# Inverter_540VDC_V2_1.net
KiCad netlist of a schematic drawn in Altium Designer
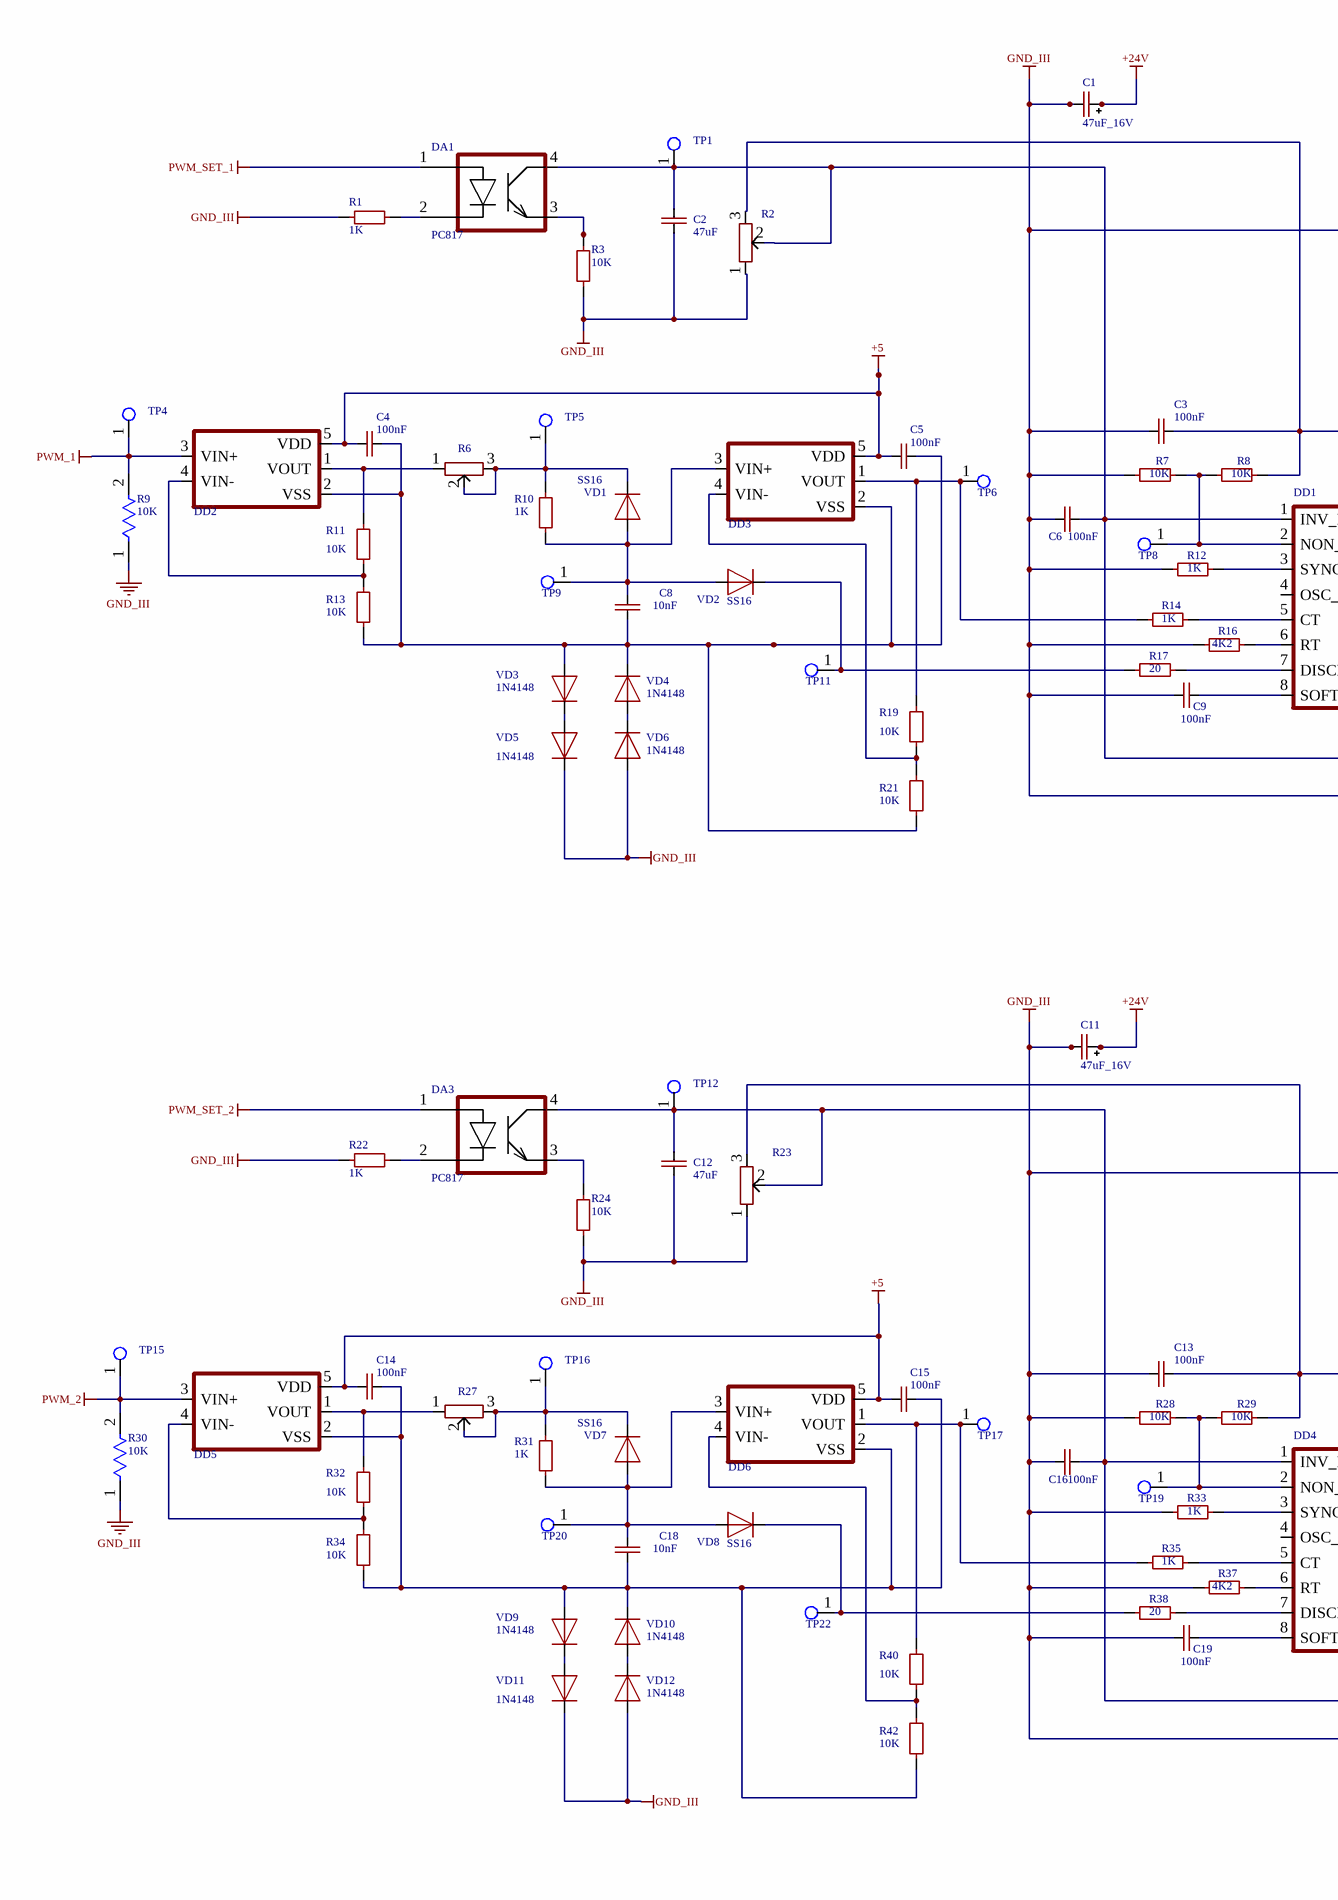
[diagram p0: Inverter_540VDC_V2.1.SchDoc, top left]
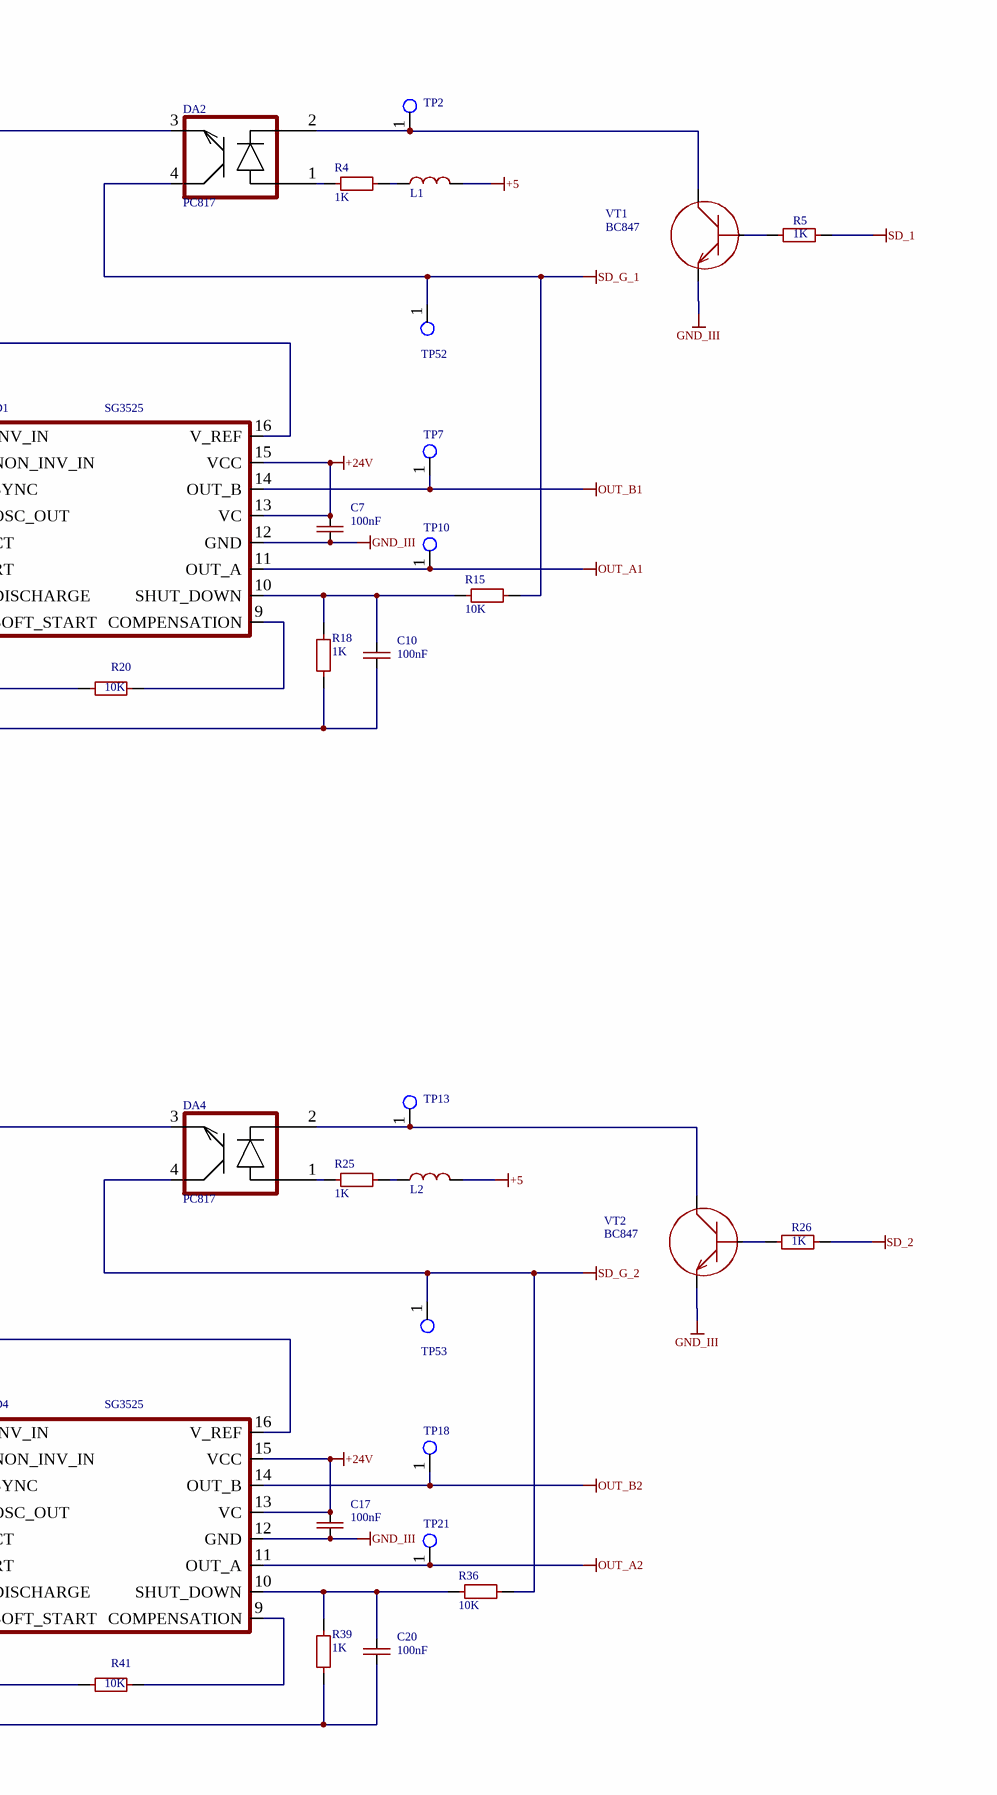
[diagram p1: Inverter_540VDC_V2.1.SchDoc, top right]
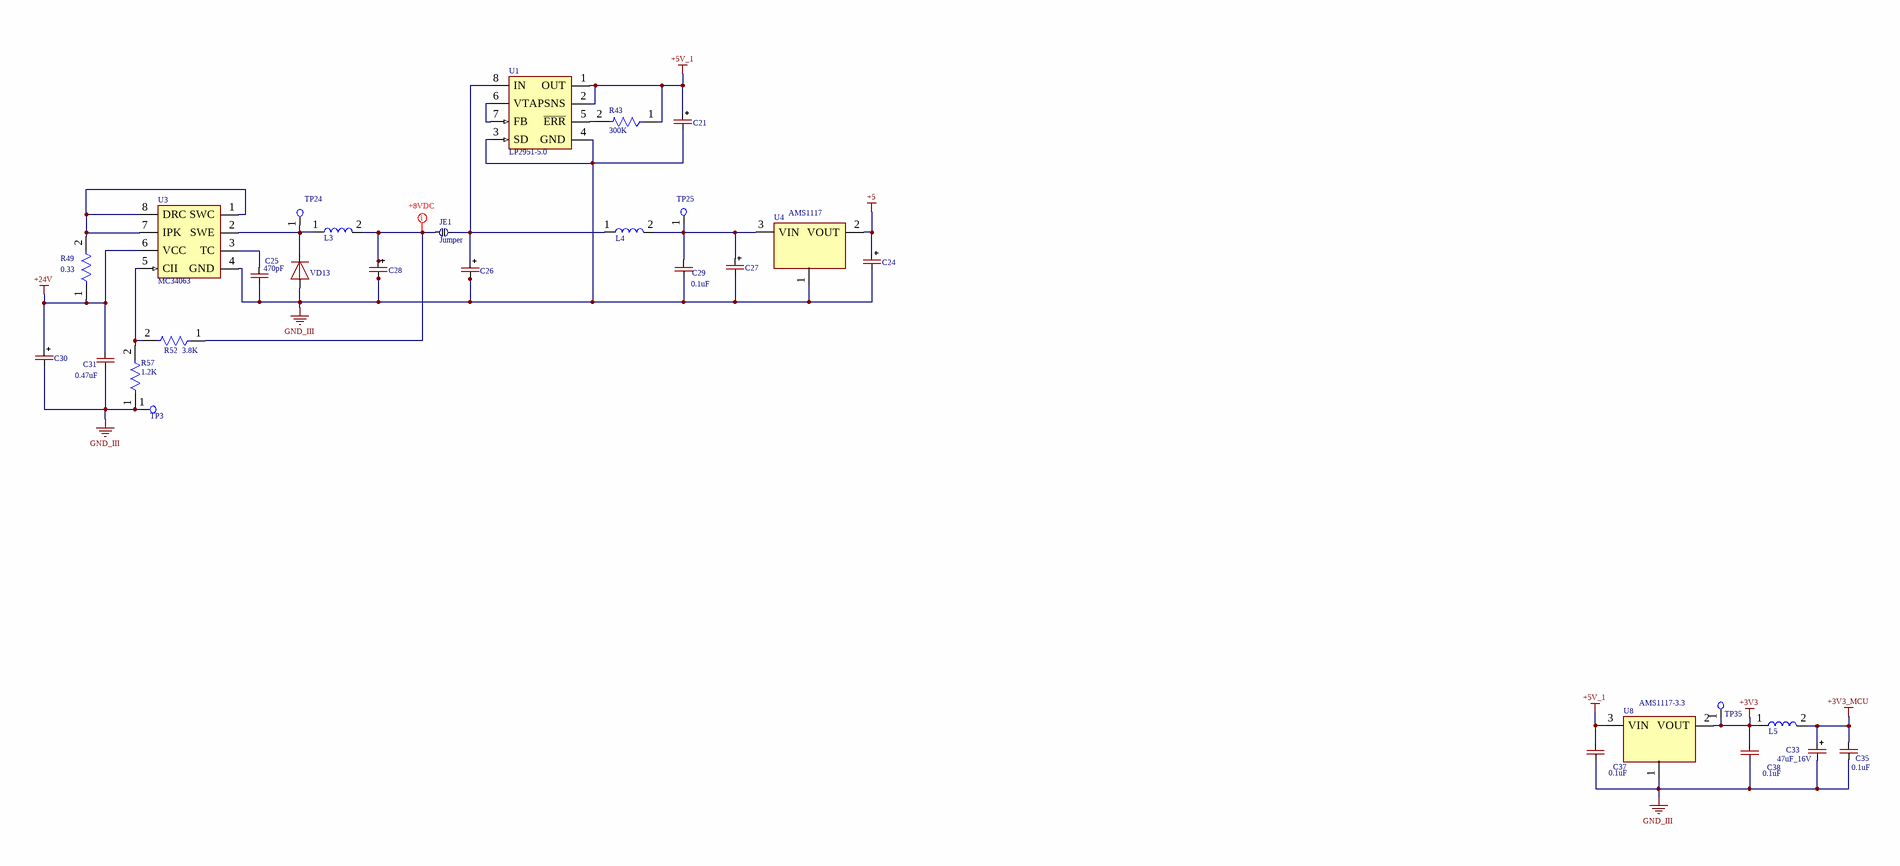
[diagram p2: Inverter_540VDC_V2.1.SchDoc, bottom left]
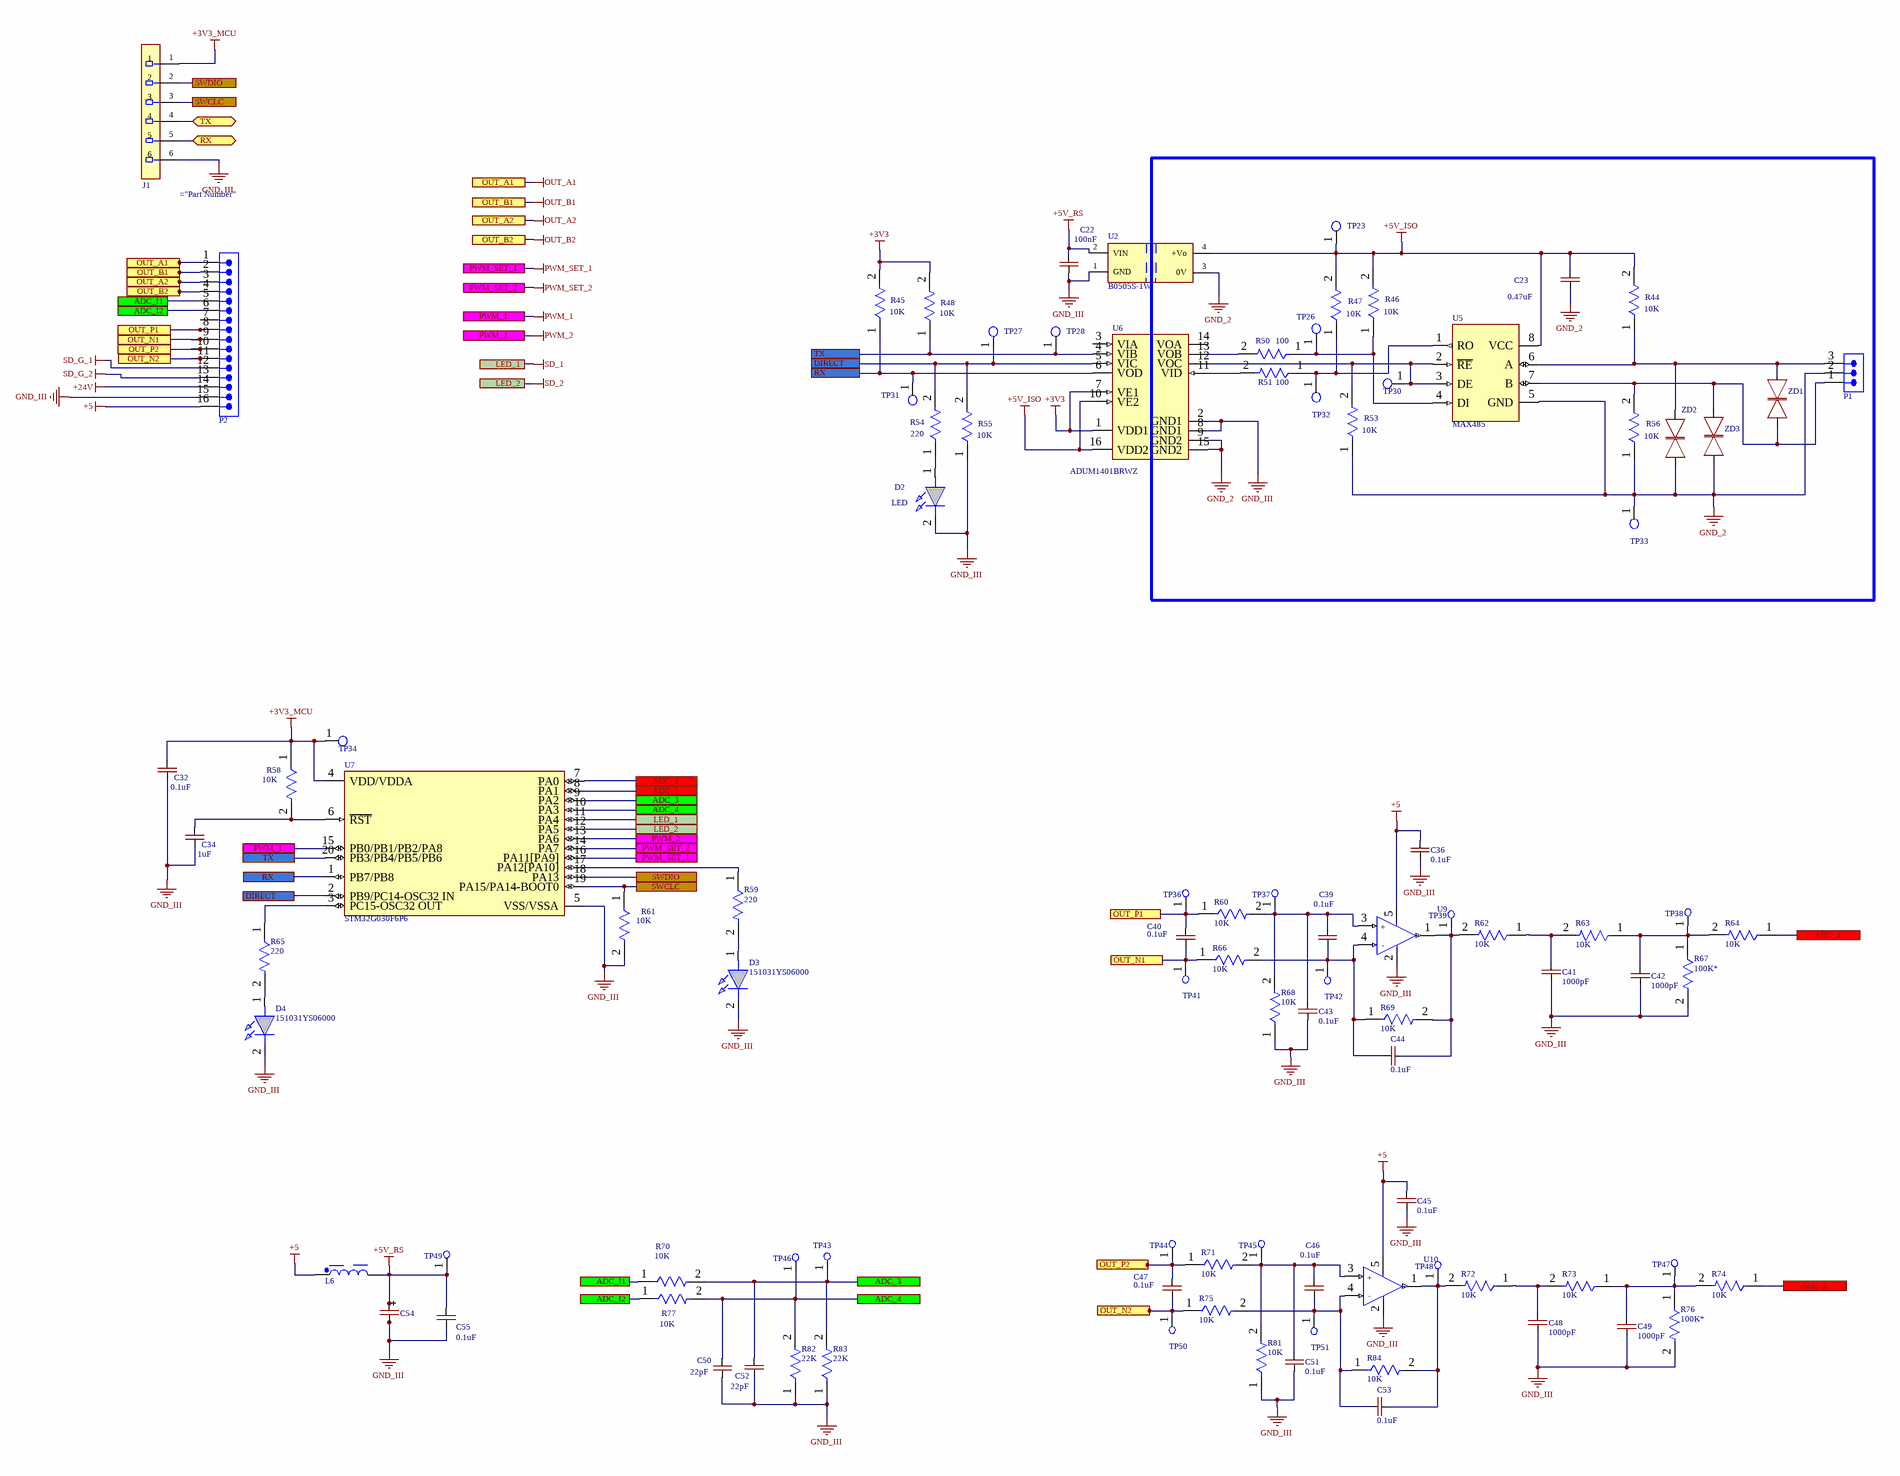
[diagram p3: Inverter_540VDC_V2.1.SchDoc, bottom right]

(export (version "E")
  (design (tool "Eeschema 10.0.6"))
  (components
    (comp (ref "C1")
      (value "47uF_16V")
      (footprint "CAP-TAN-D")
      (libsource (lib "PASSIVE_COMPONENTS") (part "CAP-POLAR"))
    )
    (comp (ref "C2")
      (value "47uF")
      (footprint "CAP-0805")
      (libsource (lib "PAS_COMPONENTS") (part "CAP-NON-POLAR"))
    )
    (comp (ref "C3")
      (value "100nF")
      (footprint "CAP-0805")
      (libsource (lib "PAS_COMPONENTS") (part "CAP-NON-POLAR"))
    )
    (comp (ref "C4")
      (value "100nF")
      (footprint "CAP-0805")
      (libsource (lib "PAS_COMPONENTS") (part "CAP-NON-POLAR"))
    )
    (comp (ref "C5")
      (value "100nF")
      (footprint "CAP-0805")
      (libsource (lib "PAS_COMPONENTS") (part "CAP-NON-POLAR"))
    )
    (comp (ref "C6")
      (value "100nF")
      (footprint "CAP-0805")
      (libsource (lib "PAS_COMPONENTS") (part "CAP-NON-POLAR"))
    )
    (comp (ref "C7")
      (value "100nF")
      (footprint "CAP-0805")
      (libsource (lib "PAS_COMPONENTS") (part "CAP-NON-POLAR"))
    )
    (comp (ref "C8")
      (value "10nF")
      (footprint "CAP-0805")
      (libsource (lib "PAS_COMPONENTS") (part "CAP-NON-POLAR"))
    )
    (comp (ref "C9")
      (value "100nF")
      (footprint "CAP-0805")
      (libsource (lib "PAS_COMPONENTS") (part "CAP-NON-POLAR"))
    )
    (comp (ref "C10")
      (value "100nF")
      (footprint "CAP-0805")
      (libsource (lib "PAS_COMPONENTS") (part "CAP-NON-POLAR"))
    )
    (comp (ref "C11")
      (value "47uF_16V")
      (footprint "CAP-TAN-D")
      (libsource (lib "PASSIVE_COMPONENTS") (part "CAP-POLAR"))
    )
    (comp (ref "C12")
      (value "47uF")
      (footprint "CAP-0805")
      (libsource (lib "PAS_COMPONENTS") (part "CAP-NON-POLAR"))
    )
    (comp (ref "C13")
      (value "100nF")
      (footprint "CAP-0805")
      (libsource (lib "PAS_COMPONENTS") (part "CAP-NON-POLAR"))
    )
    (comp (ref "C14")
      (value "100nF")
      (footprint "CAP-0805")
      (libsource (lib "PAS_COMPONENTS") (part "CAP-NON-POLAR"))
    )
    (comp (ref "C15")
      (value "100nF")
      (footprint "CAP-0805")
      (libsource (lib "PAS_COMPONENTS") (part "CAP-NON-POLAR"))
    )
    (comp (ref "C16")
      (value "100nF")
      (footprint "CAP-0805")
      (libsource (lib "PAS_COMPONENTS") (part "CAP-NON-POLAR"))
    )
    (comp (ref "C17")
      (value "100nF")
      (footprint "CAP-0805")
      (libsource (lib "PAS_COMPONENTS") (part "CAP-NON-POLAR"))
    )
    (comp (ref "C18")
      (value "10nF")
      (footprint "CAP-0805")
      (libsource (lib "PAS_COMPONENTS") (part "CAP-NON-POLAR"))
    )
    (comp (ref "C19")
      (value "100nF")
      (footprint "CAP-0805")
      (libsource (lib "PAS_COMPONENTS") (part "CAP-NON-POLAR"))
    )
    (comp (ref "C20")
      (value "100nF")
      (footprint "CAP-0805")
      (libsource (lib "PAS_COMPONENTS") (part "CAP-NON-POLAR"))
    )
    (comp (ref "C21")
      (value "CAP-POLAR")
      (footprint "CAP-TAN-C")
      (libsource (lib "PAS_COMPONENTS") (part "CAP-POLAR"))
    )
    (comp (ref "C22")
      (value "100nF")
      (footprint "CAP-0805")
      (libsource (lib "PASSIVE_COMPONENTS") (part "CAP-NON-POLAR"))
    )
    (comp (ref "C23")
      (value "0.47uF")
      (footprint "CAP-0805")
      (libsource (lib "PASSIVE_COMPONENTS") (part "CAP-NON-POLAR"))
    )
    (comp (ref "C24")
      (value "CAP-POLAR")
      (footprint "CAP-TAN-C")
      (libsource (lib "PAS_COMPONENTS") (part "CAP-POLAR"))
    )
    (comp (ref "C25")
      (value "470pF")
      (footprint "CAP-0805")
      (libsource (lib "PASSIVE_COMPONENTS") (part "CAP-NON-POLAR"))
    )
    (comp (ref "C26")
      (value "CAP-POLAR")
      (footprint "CAP-TAN-C")
      (libsource (lib "PAS_COMPONENTS") (part "CAP-POLAR"))
    )
    (comp (ref "C27")
      (value "CAP-POLAR")
      (footprint "CAP-TAN-C")
      (libsource (lib "PAS_COMPONENTS") (part "CAP-POLAR"))
    )
    (comp (ref "C28")
      (value "CAP-POLAR")
      (footprint "CAP-TAN-C")
      (libsource (lib "PAS_COMPONENTS") (part "CAP-POLAR"))
    )
    (comp (ref "C29")
      (value "0.1uF")
      (footprint "CAP-0805")
      (libsource (lib "PASSIVE_COMPONENTS") (part "CAP-NON-POLAR"))
    )
    (comp (ref "C30")
      (value "CAP-POLAR")
      (footprint "CAP-TAN-C")
      (libsource (lib "PAS_COMPONENTS") (part "CAP-POLAR"))
    )
    (comp (ref "C31")
      (value "0.47uF")
      (footprint "CAP-0805")
      (libsource (lib "PASSIVE_COMPONENTS") (part "CAP-NON-POLAR"))
    )
    (comp (ref "C32")
      (value "0.1uF")
      (footprint "CAP-0805")
      (libsource (lib "PASSIVE_COMPONENTS") (part "CAP-NON-POLAR"))
    )
    (comp (ref "C33")
      (value "47uF_16V")
      (footprint "CAP-TAN-D")
      (libsource (lib "PASSIVE_COMPONENTS") (part "CAP-POLAR"))
    )
    (comp (ref "C34")
      (value "1uF")
      (footprint "CAP-0805")
      (libsource (lib "PASSIVE_COMPONENTS") (part "CAP-NON-POLAR"))
    )
    (comp (ref "C35")
      (value "0.1uF")
      (footprint "CAP-0805")
      (libsource (lib "PASSIVE_COMPONENTS") (part "CAP-NON-POLAR"))
    )
    (comp (ref "C36")
      (value "0.1uF")
      (footprint "CAP-0805")
      (libsource (lib "PASSIVE_COMPONENTS") (part "CAP-NON-POLAR"))
    )
    (comp (ref "C37")
      (value "0.1uF")
      (footprint "CAP-0805")
      (libsource (lib "PASSIVE_COMPONENTS") (part "CAP-NON-POLAR"))
    )
    (comp (ref "C38")
      (value "0.1uF")
      (footprint "CAP-0805")
      (libsource (lib "PASSIVE_COMPONENTS") (part "CAP-NON-POLAR"))
    )
    (comp (ref "C39")
      (value "0.1uF")
      (footprint "CAP-0805")
      (libsource (lib "PASSIVE_COMPONENTS") (part "CAP-NON-POLAR"))
    )
    (comp (ref "C40")
      (value "0.1uF")
      (footprint "CAP-0805")
      (libsource (lib "PASSIVE_COMPONENTS") (part "CAP-NON-POLAR"))
    )
    (comp (ref "C41")
      (value "1000pF")
      (footprint "CAP-0805")
      (libsource (lib "PASSIVE_COMPONENTS") (part "CAP-NON-POLAR"))
    )
    (comp (ref "C42")
      (value "1000pF")
      (footprint "CAP-0805")
      (libsource (lib "PASSIVE_COMPONENTS") (part "CAP-NON-POLAR"))
    )
    (comp (ref "C43")
      (value "0.1uF")
      (footprint "CAP-0805")
      (libsource (lib "PASSIVE_COMPONENTS") (part "CAP-NON-POLAR"))
    )
    (comp (ref "C44")
      (value "0.1uF")
      (footprint "CAP-0805")
      (libsource (lib "PASSIVE_COMPONENTS") (part "CAP-NON-POLAR"))
    )
    (comp (ref "C45")
      (value "0.1uF")
      (footprint "CAP-0805")
      (libsource (lib "PASSIVE_COMPONENTS") (part "CAP-NON-POLAR"))
    )
    (comp (ref "C46")
      (value "0.1uF")
      (footprint "CAP-0805")
      (libsource (lib "PASSIVE_COMPONENTS") (part "CAP-NON-POLAR"))
    )
    (comp (ref "C47")
      (value "0.1uF")
      (footprint "CAP-0805")
      (libsource (lib "PASSIVE_COMPONENTS") (part "CAP-NON-POLAR"))
    )
    (comp (ref "C48")
      (value "1000pF")
      (footprint "CAP-0805")
      (libsource (lib "PASSIVE_COMPONENTS") (part "CAP-NON-POLAR"))
    )
    (comp (ref "C49")
      (value "1000pF")
      (footprint "CAP-0805")
      (libsource (lib "PASSIVE_COMPONENTS") (part "CAP-NON-POLAR"))
    )
    (comp (ref "C50")
      (value "22pF")
      (footprint "CAP-0805")
      (libsource (lib "PASSIVE_COMPONENTS") (part "CAP-NON-POLAR"))
    )
    (comp (ref "C51")
      (value "0.1uF")
      (footprint "CAP-0805")
      (libsource (lib "PASSIVE_COMPONENTS") (part "CAP-NON-POLAR"))
    )
    (comp (ref "C52")
      (value "22pF")
      (footprint "CAP-0805")
      (libsource (lib "PASSIVE_COMPONENTS") (part "CAP-NON-POLAR"))
    )
    (comp (ref "C53")
      (value "0.1uF")
      (footprint "CAP-0805")
      (libsource (lib "PASSIVE_COMPONENTS") (part "CAP-NON-POLAR"))
    )
    (comp (ref "C54")
      (value "CAP-POLAR")
      (footprint "CAP-TAN-C")
      (libsource (lib "PAS_COMPONENTS") (part "CAP-POLAR"))
    )
    (comp (ref "C55")
      (value "0.1uF")
      (footprint "CAP-0805")
      (libsource (lib "PASSIVE_COMPONENTS") (part "CAP-NON-POLAR"))
    )
    (comp (ref "D2")
      (value "LED")
      (footprint "LED_RED")
      (description "WURTH ELEKTRONIK - 151031YS06000 - LED, Yellow, Through Hole, T-1 (3mm), 30 mA, 2 V, 590 nm")
      (fields
        (field (name "MANUFACTURER_PART_NUMBER") "151031YS06000")
        (field (name "MOUSER PART NUMBER") "710-151031YS06000")
      )
      (libsource (lib "Optic-LED") (part "LED"))
    )
    (comp (ref "D3")
      (value "151031YS06000")
      (footprint "LED_RED")
      (description "WURTH ELEKTRONIK - 151031YS06000 - LED, Yellow, Through Hole, T-1 (3mm), 30 mA, 2 V, 590 nm")
      (fields (field (name "MOUSER PART NUMBER") "710-151031YS06000"))
      (libsource (lib "Optic-LED") (part "LED"))
    )
    (comp (ref "D4")
      (value "151031YS06000")
      (footprint "LED_RED")
      (description "WURTH ELEKTRONIK - 151031YS06000 - LED, Yellow, Through Hole, T-1 (3mm), 30 mA, 2 V, 590 nm")
      (fields (field (name "MOUSER PART NUMBER") "710-151031YS06000"))
      (libsource (lib "Optic-LED") (part "LED"))
    )
    (comp (ref "DA1") (value "PC817") (footprint "4-SMD") (libsource (lib "PC817") (part "PC817")))
    (comp (ref "DA2") (value "PC817") (footprint "4-SMD") (libsource (lib "") (part "PC817_1")))
    (comp (ref "DA3") (value "PC817") (footprint "4-SMD") (libsource (lib "PC817") (part "PC817")))
    (comp (ref "DA4") (value "PC817") (footprint "4-SMD") (libsource (lib "") (part "PC817_1")))
    (comp (ref "DD1") (value "SG3525") (footprint "SO16-150") (libsource (lib "SG3525") (part "SG3525")))
    (comp (ref "DD2") (value "MCP6001") (footprint "SOT23-5") (libsource (lib "MCP6001") (part "MCP6001")))
    (comp (ref "DD3") (value "MCP6001") (footprint "SOT23-5") (libsource (lib "MCP6001") (part "MCP6001")))
    (comp (ref "DD4") (value "SG3525") (footprint "SO16-150") (libsource (lib "SG3525") (part "SG3525")))
    (comp (ref "DD5") (value "MCP6001") (footprint "SOT23-5") (libsource (lib "MCP6001") (part "MCP6001")))
    (comp (ref "DD6") (value "MCP6001") (footprint "SOT23-5") (libsource (lib "MCP6001") (part "MCP6001")))
    (comp (ref "J1")
      (value "SWR25X-NRTC-S06-ST-BA")
      (footprint "Sullins_SWR25X-NRTC-S06-ST-BA_MFG")
      (libsource (lib "Conn_Sullins_SWR25X-NRTC-S06-ST-BA_eec") (part "SWR25X-NRTC-S06-ST-BA"))
    )
    (comp (ref "JE1") (value "Jumper") (footprint "JE") (libsource (lib "Connectors") (part "JE")))
    (comp (ref "L1")
      (value "IND-CONST")
      (footprint "IND-5852")
      (libsource (lib "PAS_COMPONENTS") (part "IND-CONST"))
    )
    (comp (ref "L2")
      (value "IND-CONST")
      (footprint "IND-5852")
      (libsource (lib "PAS_COMPONENTS") (part "IND-CONST"))
    )
    (comp (ref "L3")
      (value "Coil")
      (footprint "Coil_4.5x4.5_mm")
      (libsource (lib "Transformers") (part "Coil"))
    )
    (comp (ref "L4")
      (value "Coil")
      (footprint "Coil_4.5x4.5_mm")
      (libsource (lib "Transformers") (part "Coil"))
    )
    (comp (ref "L5")
      (value "Coil")
      (footprint "Coil_4.5x4.5_mm")
      (libsource (lib "Transformers") (part "Coil"))
    )
    (comp (ref "L6")
      (value "1000µH, 0.3A")
      (footprint "WE-PD2_7850")
      (description "WE-PD2 SMT Power Inductor, size 7850, 1000µH, 0.3A, 3.3Ω")
      (fields
        (field (name "MANUFACTURER PART NUMBER") "74477530")
        (field (name "MANUFACTURER") "Wurth Elektronik")
      )
      (libsource (lib "WE-PD2 (rev22d)") (part "74477530"))
    )
    (comp (ref "P1")
      (value "691701530003B")
      (footprint "691701530003B")
      (description "WR-TBL Series 7015B Open Horizontal PCB Header, SMT, pitch 5.08mm, 3p")
      (fields (field (name "MANUFACTURER") "Wurth Elektronik"))
      (libsource (lib "Altium_WR-TBL (rev23d)") (part "691701530003B"))
    )
    (comp (ref "P2")
      (value "61301611021")
      (footprint "61301611021")
      (description "WR-PHD Pin Header, THT, Angled, pitch 2.54mm, 1 Row, 16P")
      (fields (field (name "MANUFACTURER") "Wurth Elektronik"))
      (libsource (lib "Altium_WR-PHD (rev22b)") (part "61301611021"))
    )
    (comp (ref "R1")
      (value "1K")
      (footprint "RES-0805")
      (description "10K")
      (libsource (lib "PAS_COMPONENTS") (part "RES-CONST"))
    )
    (comp (ref "R2") (value "3296") (footprint "3296W") (libsource (lib "") (part "3296_1")))
    (comp (ref "R3")
      (value "10K")
      (footprint "RES-0805")
      (libsource (lib "PAS_COMPONENTS") (part "RES-CONST"))
    )
    (comp (ref "R4")
      (value "1K")
      (footprint "RES-0805")
      (libsource (lib "PAS_COMPONENTS") (part "RES-CONST"))
    )
    (comp (ref "R5")
      (value "1K")
      (footprint "RES-0805")
      (libsource (lib "PAS_COMPONENTS") (part "RES-CONST"))
    )
    (comp (ref "R6") (value "3296") (footprint "3296W") (libsource (lib "3296") (part "3296")))
    (comp (ref "R7")
      (value "10K")
      (footprint "RES-0805")
      (libsource (lib "PAS_COMPONENTS") (part "RES-CONST"))
    )
    (comp (ref "R8")
      (value "10K")
      (footprint "RES-0805")
      (libsource (lib "PAS_COMPONENTS") (part "RES-CONST"))
    )
    (comp (ref "R9")
      (value "10K")
      (footprint "RES-0805")
      (libsource (lib "PASSIVE_COMPONENTS") (part "RES-CONST"))
    )
    (comp (ref "R10")
      (value "1K")
      (footprint "RES-0805")
      (libsource (lib "PAS_COMPONENTS") (part "RES-CONST"))
    )
    (comp (ref "R11")
      (value "10K")
      (footprint "RES-0805")
      (libsource (lib "PAS_COMPONENTS") (part "RES-CONST"))
    )
    (comp (ref "R12")
      (value "1K")
      (footprint "RES-0805")
      (libsource (lib "PAS_COMPONENTS") (part "RES-CONST"))
    )
    (comp (ref "R13")
      (value "10K")
      (footprint "RES-0805")
      (libsource (lib "PAS_COMPONENTS") (part "RES-CONST"))
    )
    (comp (ref "R14")
      (value "1K")
      (footprint "RES-0805")
      (libsource (lib "PAS_COMPONENTS") (part "RES-CONST"))
    )
    (comp (ref "R15")
      (value "10K")
      (footprint "RES-0805")
      (libsource (lib "PAS_COMPONENTS") (part "RES-CONST"))
    )
    (comp (ref "R16")
      (value "4K2")
      (footprint "RES-0805")
      (libsource (lib "PAS_COMPONENTS") (part "RES-CONST"))
    )
    (comp (ref "R17")
      (value "20")
      (footprint "RES-0805")
      (description "1K")
      (libsource (lib "PAS_COMPONENTS") (part "RES-CONST"))
    )
    (comp (ref "R18")
      (value "1K")
      (footprint "RES-0805")
      (libsource (lib "PAS_COMPONENTS") (part "RES-CONST"))
    )
    (comp (ref "R19")
      (value "10K")
      (footprint "RES-0805")
      (libsource (lib "PAS_COMPONENTS") (part "RES-CONST"))
    )
    (comp (ref "R20")
      (value "10K")
      (footprint "RES-0805")
      (libsource (lib "PAS_COMPONENTS") (part "RES-CONST"))
    )
    (comp (ref "R21")
      (value "10K")
      (footprint "RES-0805")
      (libsource (lib "PAS_COMPONENTS") (part "RES-CONST"))
    )
    (comp (ref "R22")
      (value "1K")
      (footprint "RES-0805")
      (description "10K")
      (libsource (lib "PAS_COMPONENTS") (part "RES-CONST"))
    )
    (comp (ref "R23") (value "3296W") (footprint "3296W") (libsource (lib "3296W") (part "3296W")))
    (comp (ref "R24")
      (value "10K")
      (footprint "RES-0805")
      (libsource (lib "PAS_COMPONENTS") (part "RES-CONST"))
    )
    (comp (ref "R25")
      (value "1K")
      (footprint "RES-0805")
      (libsource (lib "PAS_COMPONENTS") (part "RES-CONST"))
    )
    (comp (ref "R26")
      (value "1K")
      (footprint "RES-0805")
      (libsource (lib "PAS_COMPONENTS") (part "RES-CONST"))
    )
    (comp (ref "R27") (value "3296") (footprint "3296W") (libsource (lib "3296") (part "3296")))
    (comp (ref "R28")
      (value "10K")
      (footprint "RES-0805")
      (libsource (lib "PAS_COMPONENTS") (part "RES-CONST"))
    )
    (comp (ref "R29")
      (value "10K")
      (footprint "RES-0805")
      (libsource (lib "PAS_COMPONENTS") (part "RES-CONST"))
    )
    (comp (ref "R30")
      (value "10K")
      (footprint "RES-0805")
      (libsource (lib "PASSIVE_COMPONENTS") (part "RES-CONST"))
    )
    (comp (ref "R31")
      (value "1K")
      (footprint "RES-0805")
      (libsource (lib "PAS_COMPONENTS") (part "RES-CONST"))
    )
    (comp (ref "R32")
      (value "10K")
      (footprint "RES-0805")
      (libsource (lib "PAS_COMPONENTS") (part "RES-CONST"))
    )
    (comp (ref "R33")
      (value "1K")
      (footprint "RES-0805")
      (libsource (lib "PAS_COMPONENTS") (part "RES-CONST"))
    )
    (comp (ref "R34")
      (value "10K")
      (footprint "RES-0805")
      (libsource (lib "PAS_COMPONENTS") (part "RES-CONST"))
    )
    (comp (ref "R35")
      (value "1K")
      (footprint "RES-0805")
      (libsource (lib "PAS_COMPONENTS") (part "RES-CONST"))
    )
    (comp (ref "R36")
      (value "10K")
      (footprint "RES-0805")
      (libsource (lib "PAS_COMPONENTS") (part "RES-CONST"))
    )
    (comp (ref "R37")
      (value "4K2")
      (footprint "RES-0805")
      (libsource (lib "PAS_COMPONENTS") (part "RES-CONST"))
    )
    (comp (ref "R38")
      (value "20")
      (footprint "RES-0805")
      (description "1K")
      (libsource (lib "PAS_COMPONENTS") (part "RES-CONST"))
    )
    (comp (ref "R39")
      (value "1K")
      (footprint "RES-0805")
      (libsource (lib "PAS_COMPONENTS") (part "RES-CONST"))
    )
    (comp (ref "R40")
      (value "10K")
      (footprint "RES-0805")
      (libsource (lib "PAS_COMPONENTS") (part "RES-CONST"))
    )
    (comp (ref "R41")
      (value "10K")
      (footprint "RES-0805")
      (libsource (lib "PAS_COMPONENTS") (part "RES-CONST"))
    )
    (comp (ref "R42")
      (value "10K")
      (footprint "RES-0805")
      (libsource (lib "PAS_COMPONENTS") (part "RES-CONST"))
    )
    (comp (ref "R43")
      (value "300K")
      (footprint "RES-0805")
      (libsource (lib "PASSIVE_COMPONENTS") (part "RES-CONST"))
    )
    (comp (ref "R44")
      (value "10K")
      (footprint "RES-0805")
      (libsource (lib "PASSIVE_COMPONENTS") (part "RES-CONST"))
    )
    (comp (ref "R45")
      (value "10K")
      (footprint "RES-0805")
      (libsource (lib "PASSIVE_COMPONENTS") (part "RES-CONST"))
    )
    (comp (ref "R46")
      (value "10K")
      (footprint "RES-0805")
      (libsource (lib "PASSIVE_COMPONENTS") (part "RES-CONST"))
    )
    (comp (ref "R47")
      (value "10K")
      (footprint "RES-0805")
      (libsource (lib "PASSIVE_COMPONENTS") (part "RES-CONST"))
    )
    (comp (ref "R48")
      (value "10K")
      (footprint "RES-0805")
      (libsource (lib "PASSIVE_COMPONENTS") (part "RES-CONST"))
    )
    (comp (ref "R49")
      (value "0.33")
      (footprint "RES-1206")
      (libsource (lib "PASSIVE_COMPONENTS") (part "RES-CONST"))
    )
    (comp (ref "R50")
      (value "100")
      (footprint "RES-0805")
      (libsource (lib "PASSIVE_COMPONENTS") (part "RES-CONST"))
    )
    (comp (ref "R51")
      (value "100")
      (footprint "RES-0805")
      (libsource (lib "PASSIVE_COMPONENTS") (part "RES-CONST"))
    )
    (comp (ref "R52")
      (value "3.8K")
      (footprint "RES-0805")
      (description "10K")
      (libsource (lib "PASSIVE_COMPONENTS") (part "RES-CONST"))
    )
    (comp (ref "R53")
      (value "10K")
      (footprint "RES-0805")
      (libsource (lib "PASSIVE_COMPONENTS") (part "RES-CONST"))
    )
    (comp (ref "R54")
      (value "220")
      (footprint "RES-0805")
      (libsource (lib "PASSIVE_COMPONENTS") (part "RES-CONST"))
    )
    (comp (ref "R55")
      (value "10K")
      (footprint "RES-0805")
      (libsource (lib "PASSIVE_COMPONENTS") (part "RES-CONST"))
    )
    (comp (ref "R56")
      (value "10K")
      (footprint "RES-0805")
      (libsource (lib "PASSIVE_COMPONENTS") (part "RES-CONST"))
    )
    (comp (ref "R57")
      (value "1.2K")
      (footprint "RES-0805")
      (libsource (lib "PASSIVE_COMPONENTS") (part "RES-CONST"))
    )
    (comp (ref "R58")
      (value "10K")
      (footprint "RES-0805")
      (libsource (lib "PASSIVE_COMPONENTS") (part "RES-CONST"))
    )
    (comp (ref "R59")
      (value "220")
      (footprint "RES-0805")
      (libsource (lib "PASSIVE_COMPONENTS") (part "RES-CONST"))
    )
    (comp (ref "R60")
      (value "10K")
      (footprint "RES-0805")
      (libsource (lib "PASSIVE_COMPONENTS") (part "RES-CONST"))
    )
    (comp (ref "R61")
      (value "10K")
      (footprint "RES-0805")
      (libsource (lib "PASSIVE_COMPONENTS") (part "RES-CONST"))
    )
    (comp (ref "R62")
      (value "10K")
      (footprint "RES-0805")
      (libsource (lib "PASSIVE_COMPONENTS") (part "RES-CONST"))
    )
    (comp (ref "R63")
      (value "10K")
      (footprint "RES-0805")
      (libsource (lib "PASSIVE_COMPONENTS") (part "RES-CONST"))
    )
    (comp (ref "R64")
      (value "10K")
      (footprint "RES-0805")
      (libsource (lib "PASSIVE_COMPONENTS") (part "RES-CONST"))
    )
    (comp (ref "R65")
      (value "220")
      (footprint "RES-0805")
      (libsource (lib "PASSIVE_COMPONENTS") (part "RES-CONST"))
    )
    (comp (ref "R66")
      (value "10K")
      (footprint "RES-0805")
      (libsource (lib "PASSIVE_COMPONENTS") (part "RES-CONST"))
    )
    (comp (ref "R67")
      (value "100K*")
      (footprint "RES-0805")
      (libsource (lib "PASSIVE_COMPONENTS") (part "RES-CONST"))
    )
    (comp (ref "R68")
      (value "10K")
      (footprint "RES-0805")
      (libsource (lib "PASSIVE_COMPONENTS") (part "RES-CONST"))
    )
    (comp (ref "R69")
      (value "10K")
      (footprint "RES-0805")
      (libsource (lib "PASSIVE_COMPONENTS") (part "RES-CONST"))
    )
    (comp (ref "R70")
      (value "10K")
      (footprint "RES-0805")
      (libsource (lib "PASSIVE_COMPONENTS") (part "RES-CONST"))
    )
    (comp (ref "R71")
      (value "10K")
      (footprint "RES-0805")
      (libsource (lib "PASSIVE_COMPONENTS") (part "RES-CONST"))
    )
    (comp (ref "R72")
      (value "10K")
      (footprint "RES-0805")
      (libsource (lib "PASSIVE_COMPONENTS") (part "RES-CONST"))
    )
    (comp (ref "R73")
      (value "10K")
      (footprint "RES-0805")
      (libsource (lib "PASSIVE_COMPONENTS") (part "RES-CONST"))
    )
    (comp (ref "R74")
      (value "10K")
      (footprint "RES-0805")
      (libsource (lib "PASSIVE_COMPONENTS") (part "RES-CONST"))
    )
    (comp (ref "R75")
      (value "10K")
      (footprint "RES-0805")
      (libsource (lib "PASSIVE_COMPONENTS") (part "RES-CONST"))
    )
    (comp (ref "R76")
      (value "100K*")
      (footprint "RES-0805")
      (libsource (lib "PASSIVE_COMPONENTS") (part "RES-CONST"))
    )
    (comp (ref "R77")
      (value "10K")
      (footprint "RES-0805")
      (libsource (lib "PASSIVE_COMPONENTS") (part "RES-CONST"))
    )
    (comp (ref "R81")
      (value "10K")
      (footprint "RES-0805")
      (libsource (lib "PASSIVE_COMPONENTS") (part "RES-CONST"))
    )
    (comp (ref "R82")
      (value "22K")
      (footprint "RES-0805")
      (libsource (lib "PASSIVE_COMPONENTS") (part "RES-CONST"))
    )
    (comp (ref "R83")
      (value "22K")
      (footprint "RES-0805")
      (libsource (lib "PASSIVE_COMPONENTS") (part "RES-CONST"))
    )
    (comp (ref "R84")
      (value "10K")
      (footprint "RES-0805")
      (libsource (lib "PASSIVE_COMPONENTS") (part "RES-CONST"))
    )
    (comp (ref "TP1")
      (value "Test_Point_PCB")
      (footprint "Test_Point")
      (description "Test_Point")
      (libsource (lib "TEST_POINT") (part "TP_PCB?"))
    )
    (comp (ref "TP2")
      (value "Test_Point_PCB")
      (footprint "Test_Point")
      (description "Test_Point")
      (libsource (lib "TEST_POINT") (part "TP_PCB?"))
    )
    (comp (ref "TP3")
      (value "Test_Point_PCB")
      (footprint "Test_Point")
      (description "Test_Point")
      (libsource (lib "Connectors") (part "TP_PCB?"))
    )
    (comp (ref "TP4")
      (value "Test_Point_PCB")
      (footprint "Test_Point")
      (description "Test_Point")
      (libsource (lib "TEST_POINT") (part "TP_PCB?"))
    )
    (comp (ref "TP5")
      (value "Test_Point_PCB")
      (footprint "Test_Point")
      (description "Test_Point")
      (libsource (lib "TEST_POINT") (part "TP_PCB?"))
    )
    (comp (ref "TP6")
      (value "Test_Point_PCB")
      (footprint "Test_Point")
      (description "Test_Point")
      (libsource (lib "TEST_POINT") (part "TP_PCB?"))
    )
    (comp (ref "TP7")
      (value "Test_Point_PCB")
      (footprint "Test_Point")
      (description "Test_Point")
      (libsource (lib "TEST_POINT") (part "TP_PCB?"))
    )
    (comp (ref "TP8")
      (value "Test_Point_PCB")
      (footprint "Test_Point")
      (description "Test_Point")
      (libsource (lib "TEST_POINT") (part "TP_PCB?"))
    )
    (comp (ref "TP9")
      (value "Test_Point_PCB")
      (footprint "Test_Point")
      (description "Test_Point")
      (libsource (lib "TEST_POINT") (part "TP_PCB?"))
    )
    (comp (ref "TP10")
      (value "Test_Point_PCB")
      (footprint "Test_Point")
      (description "Test_Point")
      (libsource (lib "TEST_POINT") (part "TP_PCB?"))
    )
    (comp (ref "TP11")
      (value "Test_Point_PCB")
      (footprint "Test_Point")
      (description "Test_Point")
      (libsource (lib "TEST_POINT") (part "TP_PCB?"))
    )
    (comp (ref "TP12")
      (value "Test_Point_PCB")
      (footprint "Test_Point")
      (description "Test_Point")
      (libsource (lib "TEST_POINT") (part "TP_PCB?"))
    )
    (comp (ref "TP13")
      (value "Test_Point_PCB")
      (footprint "Test_Point")
      (description "Test_Point")
      (libsource (lib "TEST_POINT") (part "TP_PCB?"))
    )
    (comp (ref "TP15")
      (value "Test_Point_PCB")
      (footprint "Test_Point")
      (description "Test_Point")
      (libsource (lib "TEST_POINT") (part "TP_PCB?"))
    )
    (comp (ref "TP16")
      (value "Test_Point_PCB")
      (footprint "Test_Point")
      (description "Test_Point")
      (libsource (lib "TEST_POINT") (part "TP_PCB?"))
    )
    (comp (ref "TP17")
      (value "Test_Point_PCB")
      (footprint "Test_Point")
      (description "Test_Point")
      (libsource (lib "TEST_POINT") (part "TP_PCB?"))
    )
    (comp (ref "TP18")
      (value "Test_Point_PCB")
      (footprint "Test_Point")
      (description "Test_Point")
      (libsource (lib "TEST_POINT") (part "TP_PCB?"))
    )
    (comp (ref "TP19")
      (value "Test_Point_PCB")
      (footprint "Test_Point")
      (description "Test_Point")
      (libsource (lib "TEST_POINT") (part "TP_PCB?"))
    )
    (comp (ref "TP20")
      (value "Test_Point_PCB")
      (footprint "Test_Point")
      (description "Test_Point")
      (libsource (lib "TEST_POINT") (part "TP_PCB?"))
    )
    (comp (ref "TP21")
      (value "Test_Point_PCB")
      (footprint "Test_Point")
      (description "Test_Point")
      (libsource (lib "TEST_POINT") (part "TP_PCB?"))
    )
    (comp (ref "TP22")
      (value "Test_Point_PCB")
      (footprint "Test_Point")
      (description "Test_Point")
      (libsource (lib "TEST_POINT") (part "TP_PCB?"))
    )
    (comp (ref "TP23")
      (value "Test_Point_PCB")
      (footprint "Test_Point")
      (description "Test_Point")
      (libsource (lib "Test_Point") (part "TP_PCB?"))
    )
    (comp (ref "TP24")
      (value "Test_Point_PCB")
      (footprint "Test_Point")
      (description "Test_Point")
      (libsource (lib "Connectors") (part "TP_PCB?"))
    )
    (comp (ref "TP25")
      (value "Test_Point_PCB")
      (footprint "Test_Point")
      (description "Test_Point")
      (libsource (lib "Connectors") (part "TP_PCB?"))
    )
    (comp (ref "TP26")
      (value "Test_Point_PCB")
      (footprint "Test_Point")
      (description "Test_Point")
      (libsource (lib "Test_Point") (part "TP_PCB?"))
    )
    (comp (ref "TP27")
      (value "Test_Point_PCB")
      (footprint "Test_Point")
      (description "Test_Point")
      (libsource (lib "Test_Point") (part "TP_PCB?"))
    )
    (comp (ref "TP28")
      (value "Test_Point_PCB")
      (footprint "Test_Point")
      (description "Test_Point")
      (libsource (lib "Test_Point") (part "TP_PCB?"))
    )
    (comp (ref "TP30")
      (value "Test_Point_PCB")
      (footprint "Test_Point")
      (description "Test_Point")
      (libsource (lib "Test_Point") (part "TP_PCB?"))
    )
    (comp (ref "TP31")
      (value "Test_Point_PCB")
      (footprint "Test_Point")
      (description "Test_Point")
      (libsource (lib "Test_Point") (part "TP_PCB?"))
    )
    (comp (ref "TP32")
      (value "~")
      (footprint "Test_Point")
      (description "Test_Point")
      (libsource (lib "") (part "TP_PCB?_1"))
    )
    (comp (ref "TP33")
      (value "Test_Point_PCB")
      (footprint "Test_Point")
      (description "Test_Point")
      (libsource (lib "Test_Point") (part "TP_PCB?"))
    )
    (comp (ref "TP34")
      (value "~")
      (footprint "Test_Point")
      (description "Test_Point")
      (libsource (lib "") (part "TP_PCB?_1"))
    )
    (comp (ref "TP35")
      (value "Test_Point_PCB")
      (footprint "Test_Point")
      (description "Test_Point")
      (libsource (lib "Connectors") (part "TP_PCB?"))
    )
    (comp (ref "TP36")
      (value "Test_Point_PCB")
      (footprint "Test_Point")
      (description "Test_Point")
      (libsource (lib "Connectors") (part "TP_PCB?"))
    )
    (comp (ref "TP37")
      (value "Test_Point_PCB")
      (footprint "Test_Point")
      (description "Test_Point")
      (libsource (lib "Connectors") (part "TP_PCB?"))
    )
    (comp (ref "TP38")
      (value "Test_Point_PCB")
      (footprint "Test_Point")
      (description "Test_Point")
      (libsource (lib "Connectors") (part "TP_PCB?"))
    )
    (comp (ref "TP39")
      (value "Test_Point_PCB")
      (footprint "Test_Point")
      (description "Test_Point")
      (libsource (lib "Connectors") (part "TP_PCB?"))
    )
    (comp (ref "TP41")
      (value "Test_Point_PCB")
      (footprint "Test_Point")
      (description "Test_Point")
      (libsource (lib "Connectors") (part "TP_PCB?"))
    )
    (comp (ref "TP42")
      (value "Test_Point_PCB")
      (footprint "Test_Point")
      (description "Test_Point")
      (libsource (lib "Connectors") (part "TP_PCB?"))
    )
    (comp (ref "TP43")
      (value "Test_Point_PCB")
      (footprint "Test_Point")
      (description "Test_Point")
      (libsource (lib "Connectors") (part "TP_PCB?"))
    )
    (comp (ref "TP44")
      (value "Test_Point_PCB")
      (footprint "Test_Point")
      (description "Test_Point")
      (libsource (lib "Connectors") (part "TP_PCB?"))
    )
    (comp (ref "TP45")
      (value "Test_Point_PCB")
      (footprint "Test_Point")
      (description "Test_Point")
      (libsource (lib "Connectors") (part "TP_PCB?"))
    )
    (comp (ref "TP46")
      (value "Test_Point_PCB")
      (footprint "Test_Point")
      (description "Test_Point")
      (libsource (lib "Connectors") (part "TP_PCB?"))
    )
    (comp (ref "TP47")
      (value "Test_Point_PCB")
      (footprint "Test_Point")
      (description "Test_Point")
      (libsource (lib "Connectors") (part "TP_PCB?"))
    )
    (comp (ref "TP48")
      (value "Test_Point_PCB")
      (footprint "Test_Point")
      (description "Test_Point")
      (libsource (lib "Connectors") (part "TP_PCB?"))
    )
    (comp (ref "TP49")
      (value "Test_Point_PCB")
      (footprint "Test_Point")
      (description "Test_Point")
      (libsource (lib "Connectors") (part "TP_PCB?"))
    )
    (comp (ref "TP50")
      (value "Test_Point_PCB")
      (footprint "Test_Point")
      (description "Test_Point")
      (libsource (lib "Connectors") (part "TP_PCB?"))
    )
    (comp (ref "TP51")
      (value "Test_Point_PCB")
      (footprint "Test_Point")
      (description "Test_Point")
      (libsource (lib "Connectors") (part "TP_PCB?"))
    )
    (comp (ref "TP52")
      (value "Test_Point_PCB")
      (footprint "Test_Point")
      (description "Test_Point")
      (libsource (lib "TEST_POINT") (part "TP_PCB?"))
    )
    (comp (ref "TP53")
      (value "Test_Point_PCB")
      (footprint "Test_Point")
      (description "Test_Point")
      (libsource (lib "TEST_POINT") (part "TP_PCB?"))
    )
    (comp (ref "U1")
      (value "LP2951-5.0")
      (footprint "SOIC-8_L")
      (libsource (lib "Integrated_Circuts") (part "LP2951-3.3"))
    )
    (comp (ref "U2")
      (value "B0505S-1W")
      (footprint "B0505S-1W")
      (libsource (lib "Integrated_Circuts") (part "B0505S-1W"))
    )
    (comp (ref "U3")
      (value "MC34063")
      (footprint "SOIC-8_M")
      (libsource (lib "Integrated_Circuts") (part "MC34063"))
    )
    (comp (ref "U4")
      (value "AMS1117")
      (footprint "SOT-89")
      (libsource (lib "Integrated_Circuts") (part "AMS1117"))
    )
    (comp (ref "U5")
      (value "MAX485")
      (footprint "SOIC-8-MFG")
      (libsource (lib "Integrated_Circuts") (part "MAX485"))
    )
    (comp (ref "U6")
      (value "ADUM1401BRWZ")
      (footprint "ADI-RW-16_M")
      (fields (field (name "MANUFACTURER") "Analog Devices"))
      (libsource (lib "Altium Content Vault") (part "ADI-ADUMX4X1-16"))
    )
    (comp (ref "U7")
      (value "STM32G030F6P6")
      (footprint "FP-TSSOP20-YA-IPC_A")
      (description "SOIC-20")
      (libsource (lib "Integrated_Circuts") (part "STM32G030F6P6"))
    )
    (comp (ref "U8")
      (value "AMS1117-3.3")
      (footprint "SOT-223")
      (libsource (lib "Integrated_Circuts") (part "AMS1117"))
    )
    (comp (ref "U9")
      (value "~")
      (footprint "SOT-23-5")
      (description "IC OPAMP GP 1 CIRCUIT SOT23-5")
      (fields (field (name "VOLTAGE") "6V"))
      (libsource (lib "Integrated_Circuts") (part "MCP6001T"))
    )
    (comp (ref "U10")
      (value "~")
      (footprint "SOT-23-5")
      (description "IC OPAMP GP 1 CIRCUIT SOT23-5")
      (fields (field (name "VOLTAGE") "6V"))
      (libsource (lib "Integrated_Circuts") (part "MCP6001T"))
    )
    (comp (ref "VD1") (value "SS16") (footprint "DO-214AC, SMA") (libsource (lib "DIODES") (part "DIODE")))
    (comp (ref "VD2") (value "SS16") (footprint "DO-214AC, SMA") (libsource (lib "DIODES") (part "DIODE")))
    (comp (ref "VD3") (value "1N4148") (footprint "SOD-123") (libsource (lib "DIODES") (part "DIODE")))
    (comp (ref "VD4") (value "1N4148") (footprint "SOD-123") (libsource (lib "DIODES") (part "DIODE")))
    (comp (ref "VD5") (value "1N4148") (footprint "SOD-123") (libsource (lib "DIODES") (part "DIODE")))
    (comp (ref "VD6") (value "1N4148") (footprint "SOD-123") (libsource (lib "DIODES") (part "DIODE")))
    (comp (ref "VD7") (value "SS16") (footprint "DO-214AC, SMA") (libsource (lib "DIODES") (part "DIODE")))
    (comp (ref "VD8") (value "SS16") (footprint "DO-214AC, SMA") (libsource (lib "DIODES") (part "DIODE")))
    (comp (ref "VD9") (value "1N4148") (footprint "SOD-123") (libsource (lib "DIODES") (part "DIODE")))
    (comp (ref "VD10") (value "1N4148") (footprint "SOD-123") (libsource (lib "DIODES") (part "DIODE")))
    (comp (ref "VD11") (value "1N4148") (footprint "SOD-123") (libsource (lib "DIODES") (part "DIODE")))
    (comp (ref "VD12") (value "1N4148") (footprint "SOD-123") (libsource (lib "DIODES") (part "DIODE")))
    (comp (ref "VD13") (value "DIODE") (footprint "DO-214AC, SMA") (libsource (lib "DIODES") (part "DIODE")))
    (comp (ref "VT1")
      (value "BC847")
      (footprint "SOT23-3")
      (libsource (lib "TRANSISTORS") (part "BIPOLAR-NPN-BEC"))
    )
    (comp (ref "VT2")
      (value "BC847")
      (footprint "SOT23-3")
      (libsource (lib "TRANSISTORS") (part "BIPOLAR-NPN-BEC"))
    )
    (comp (ref "ZD1")
      (value "P6SMB16CA")
      (footprint "DO-214AA")
      (libsource (lib "P6SMB16CA") (part "P6SMB16CA"))
    )
    (comp (ref "ZD2")
      (value "P6SMB16CA")
      (footprint "DO-214AA")
      (libsource (lib "P6SMB16CA") (part "P6SMB16CA"))
    )
    (comp (ref "ZD3")
      (value "P6SMB16CA")
      (footprint "DO-214AA")
      (libsource (lib "P6SMB16CA") (part "P6SMB16CA"))
    )
  )
  (nets
    (net (code "1") (name "+3V3") (class "Default")
      (node (ref "C38") (pin "2") (pinfunction "2_2") (pintype "passive"))
      (node (ref "L5") (pin "1") (pinfunction "1_1") (pintype "passive"))
      (node (ref "R45") (pin "2") (pinfunction "2_2") (pintype "passive"))
      (node (ref "R48") (pin "2") (pinfunction "2_2") (pintype "passive"))
      (node (ref "TP35") (pin "1") (pinfunction "G9_1") (pintype "passive"))
      (node (ref "U6") (pin "1") (pinfunction "VDD1_1") (pintype "power_in"))
      (node (ref "U6") (pin "7") (pinfunction "VE1_7") (pintype "input"))
      (node (ref "U8") (pin "2") (pinfunction "VOUT_2") (pintype "passive"))
    )
    (net (code "2") (name "+3V3_MCU") (class "Default")
      (node (ref "C32") (pin "2") (pinfunction "2_2") (pintype "passive"))
      (node (ref "C33") (pin "1") (pinfunction "+_1") (pintype "passive"))
      (node (ref "C35") (pin "2") (pinfunction "2_2") (pintype "passive"))
      (node (ref "J1") (pin "1") (pinfunction "1_1") (pintype "passive"))
      (node (ref "L5") (pin "2") (pinfunction "2_2") (pintype "passive"))
      (node (ref "R58") (pin "1") (pinfunction "1_1") (pintype "passive"))
      (node (ref "TP34") (pin "1") (pinfunction "G9_1") (pintype "passive"))
      (node (ref "U7") (pin "4") (pinfunction "VDD/VDDA_4") (pintype "power_in"))
    )
    (net (code "3") (name "+5") (class "Default")
      (node (ref "C14") (pin "2") (pinfunction "2_2") (pintype "passive"))
      (node (ref "C15") (pin "2") (pinfunction "2_2") (pintype "passive"))
      (node (ref "C24") (pin "1") (pinfunction "+_1") (pintype "passive"))
      (node (ref "C36") (pin "2") (pinfunction "2_2") (pintype "passive"))
      (node (ref "C4") (pin "2") (pinfunction "2_2") (pintype "passive"))
      (node (ref "C45") (pin "2") (pinfunction "2_2") (pintype "passive"))
      (node (ref "C5") (pin "2") (pinfunction "2_2") (pintype "passive"))
      (node (ref "DD2") (pin "5") (pinfunction "VDD_5") (pintype "passive"))
      (node (ref "DD3") (pin "5") (pinfunction "VDD_5") (pintype "passive"))
      (node (ref "DD5") (pin "5") (pinfunction "VDD_5") (pintype "passive"))
      (node (ref "DD6") (pin "5") (pinfunction "VDD_5") (pintype "passive"))
      (node (ref "L1") (pin "2") (pinfunction "2_2") (pintype "passive"))
      (node (ref "L2") (pin "2") (pinfunction "2_2") (pintype "passive"))
      (node (ref "L6") (pin "1") (pinfunction "1_1") (pintype "passive"))
      (node (ref "P2") (pin "16") (pinfunction "16_16") (pintype "passive"))
      (node (ref "U10") (pin "5") (pinfunction "VDD_5") (pintype "power_in"))
      (node (ref "U4") (pin "2") (pinfunction "VOUT_2") (pintype "passive"))
      (node (ref "U9") (pin "5") (pinfunction "VDD_5") (pintype "power_in"))
    )
    (net (code "4") (name "+5V_1") (class "Default")
      (node (ref "C21") (pin "1") (pinfunction "+_1") (pintype "passive"))
      (node (ref "C37") (pin "2") (pinfunction "2_2") (pintype "passive"))
      (node (ref "R43") (pin "1") (pinfunction "1_1") (pintype "passive"))
      (node (ref "U1") (pin "1") (pinfunction "OUT_1") (pintype "power_in"))
      (node (ref "U1") (pin "2") (pinfunction "SNS_2") (pintype "passive"))
      (node (ref "U8") (pin "3") (pinfunction "VIN_3") (pintype "power_in"))
    )
    (net (code "5") (name "+5V_ISO") (class "Default")
      (node (ref "C23") (pin "1") (pinfunction "1_1") (pintype "passive"))
      (node (ref "R44") (pin "2") (pinfunction "2_2") (pintype "passive"))
      (node (ref "R46") (pin "2") (pinfunction "2_2") (pintype "passive"))
      (node (ref "R47") (pin "2") (pinfunction "2_2") (pintype "passive"))
      (node (ref "TP23") (pin "1") (pinfunction "G9_1") (pintype "passive"))
      (node (ref "U2") (pin "4") (pinfunction "+Vo_4") (pintype "power_in"))
      (node (ref "U5") (pin "8") (pinfunction "VCC_8") (pintype "power_in"))
      (node (ref "U6") (pin "10") (pinfunction "VE2_10") (pintype "input"))
      (node (ref "U6") (pin "16") (pinfunction "VDD2_16") (pintype "power_in"))
    )
    (net (code "6") (name "+5V_RS") (class "Default")
      (node (ref "C22") (pin "2") (pinfunction "2_2") (pintype "passive"))
      (node (ref "C54") (pin "1") (pinfunction "+_1") (pintype "passive"))
      (node (ref "C55") (pin "2") (pinfunction "2_2") (pintype "passive"))
      (node (ref "L6") (pin "2") (pinfunction "2_2") (pintype "passive"))
      (node (ref "TP49") (pin "1") (pinfunction "G9_1") (pintype "passive"))
      (node (ref "U2") (pin "2") (pinfunction "VIN_2") (pintype "power_in"))
    )
    (net (code "7") (name "+24V") (class "Default")
      (node (ref "C1") (pin "1") (pinfunction "+_1") (pintype "passive"))
      (node (ref "C11") (pin "1") (pinfunction "+_1") (pintype "passive"))
      (node (ref "C17") (pin "2") (pinfunction "2_2") (pintype "passive"))
      (node (ref "C30") (pin "1") (pinfunction "+_1") (pintype "passive"))
      (node (ref "C31") (pin "1") (pinfunction "1_1") (pintype "passive"))
      (node (ref "C7") (pin "2") (pinfunction "2_2") (pintype "passive"))
      (node (ref "DD1") (pin "13") (pinfunction "VC_13") (pintype "passive"))
      (node (ref "DD1") (pin "15") (pinfunction "VCC_15") (pintype "passive"))
      (node (ref "DD4") (pin "13") (pinfunction "VC_13") (pintype "passive"))
      (node (ref "DD4") (pin "15") (pinfunction "VCC_15") (pintype "passive"))
      (node (ref "P2") (pin "14") (pinfunction "14_14") (pintype "passive"))
      (node (ref "R49") (pin "1") (pinfunction "1_1") (pintype "passive"))
      (node (ref "U3") (pin "6") (pinfunction "VCC_6") (pintype "power_in"))
    )
    (net (code "8") (name "/ADC_1") (class "Default")
      (node (ref "R64") (pin "1") (pinfunction "1_1") (pintype "passive"))
      (node (ref "U7") (pin "7") (pinfunction "PA0_7") (pintype "bidirectional"))
    )
    (net (code "9") (name "/ADC_2") (class "Default")
      (node (ref "R74") (pin "1") (pinfunction "1_1") (pintype "passive"))
      (node (ref "U7") (pin "8") (pinfunction "PA1_8") (pintype "bidirectional"))
    )
    (net (code "10") (name "/ADC_3") (class "Default")
      (node (ref "C52") (pin "2") (pinfunction "2_2") (pintype "passive"))
      (node (ref "R70") (pin "2") (pinfunction "2_2") (pintype "passive"))
      (node (ref "R83") (pin "2") (pinfunction "2_2") (pintype "passive"))
      (node (ref "TP43") (pin "1") (pinfunction "G9_1") (pintype "passive"))
      (node (ref "U7") (pin "9") (pinfunction "PA2_9") (pintype "bidirectional"))
    )
    (net (code "11") (name "/ADC_4") (class "Default")
      (node (ref "C50") (pin "2") (pinfunction "2_2") (pintype "passive"))
      (node (ref "R77") (pin "2") (pinfunction "2_2") (pintype "passive"))
      (node (ref "R82") (pin "2") (pinfunction "2_2") (pintype "passive"))
      (node (ref "TP46") (pin "1") (pinfunction "G9_1") (pintype "passive"))
      (node (ref "U7") (pin "10") (pinfunction "PA3_10") (pintype "bidirectional"))
    )
    (net (code "12") (name "/ADC_I1") (class "Default")
      (node (ref "P2") (pin "5") (pinfunction "5_5") (pintype "passive"))
      (node (ref "R70") (pin "1") (pinfunction "1_1") (pintype "passive"))
    )
    (net (code "13") (name "/ADC_I2") (class "Default")
      (node (ref "P2") (pin "6") (pinfunction "6_6") (pintype "passive"))
      (node (ref "R77") (pin "1") (pinfunction "1_1") (pintype "passive"))
    )
    (net (code "14") (name "/DIRECT") (class "Default")
      (node (ref "R54") (pin "2") (pinfunction "2_2") (pintype "passive"))
      (node (ref "R55") (pin "2") (pinfunction "2_2") (pintype "passive"))
      (node (ref "TP27") (pin "1") (pinfunction "G9_1") (pintype "passive"))
      (node (ref "U6") (pin "5") (pinfunction "VIC_5") (pintype "input"))
      (node (ref "U7") (pin "2") (pinfunction "PB9/PC14-OSC32_IN_2") (pintype "bidirectional"))
    )
    (net (code "15") (name "/OUT_N1") (class "Default")
      (node (ref "C40") (pin "1") (pinfunction "1_1") (pintype "passive"))
      (node (ref "P2") (pin "9") (pinfunction "9_9") (pintype "passive"))
      (node (ref "R66") (pin "1") (pinfunction "1_1") (pintype "passive"))
      (node (ref "TP41") (pin "1") (pinfunction "G9_1") (pintype "passive"))
    )
    (net (code "16") (name "/OUT_N2") (class "Default")
      (node (ref "C47") (pin "1") (pinfunction "1_1") (pintype "passive"))
      (node (ref "P2") (pin "11") (pinfunction "11_11") (pintype "passive"))
      (node (ref "R75") (pin "1") (pinfunction "1_1") (pintype "passive"))
      (node (ref "TP50") (pin "1") (pinfunction "G9_1") (pintype "passive"))
    )
    (net (code "17") (name "/OUT_P1") (class "Default")
      (node (ref "C40") (pin "2") (pinfunction "2_2") (pintype "passive"))
      (node (ref "P2") (pin "8") (pinfunction "8_8") (pintype "passive"))
      (node (ref "R60") (pin "1") (pinfunction "1_1") (pintype "passive"))
      (node (ref "TP36") (pin "1") (pinfunction "G9_1") (pintype "passive"))
    )
    (net (code "18") (name "/OUT_P2") (class "Default")
      (node (ref "C47") (pin "2") (pinfunction "2_2") (pintype "passive"))
      (node (ref "P2") (pin "10") (pinfunction "10_10") (pintype "passive"))
      (node (ref "R71") (pin "1") (pinfunction "1_1") (pintype "passive"))
      (node (ref "TP44") (pin "1") (pinfunction "G9_1") (pintype "passive"))
    )
    (net (code "19") (name "/RX") (class "Default")
      (node (ref "J1") (pin "5") (pinfunction "5_5") (pintype "passive"))
      (node (ref "R45") (pin "1") (pinfunction "1_1") (pintype "passive"))
      (node (ref "TP31") (pin "1") (pinfunction "G9_1") (pintype "passive"))
      (node (ref "U6") (pin "6") (pinfunction "VOD_6") (pintype "tri_state"))
      (node (ref "U7") (pin "1") (pinfunction "PB7/PB8_1") (pintype "bidirectional"))
    )
    (net (code "20") (name "/SWCLC") (class "Default")
      (node (ref "J1") (pin "3") (pinfunction "3_3") (pintype "passive"))
      (node (ref "R61") (pin "1") (pinfunction "1_1") (pintype "passive"))
      (node (ref "U7") (pin "19") (pinfunction "PA15/PA14-BOOT0_19") (pintype "bidirectional"))
    )
    (net (code "21") (name "/SWDIO") (class "Default")
      (node (ref "J1") (pin "2") (pinfunction "2_2") (pintype "passive"))
      (node (ref "U7") (pin "18") (pinfunction "PA13_18") (pintype "bidirectional"))
    )
    (net (code "22") (name "/TX") (class "Default")
      (node (ref "J1") (pin "4") (pinfunction "4_4") (pintype "passive"))
      (node (ref "R48") (pin "1") (pinfunction "1_1") (pintype "passive"))
      (node (ref "TP28") (pin "1") (pinfunction "G9_1") (pintype "passive"))
      (node (ref "U6") (pin "4") (pinfunction "VIB_4") (pintype "input"))
      (node (ref "U7") (pin "20") (pinfunction "PB3/PB4/PB5/PB6_20") (pintype "bidirectional"))
    )
    (net (code "23") (name "GND_2") (class "Default")
      (node (ref "C23") (pin "2") (pinfunction "2_2") (pintype "passive"))
      (node (ref "P1") (pin "2") (pinfunction "2_2") (pintype "passive"))
      (node (ref "R53") (pin "1") (pinfunction "1_1") (pintype "passive"))
      (node (ref "R56") (pin "1") (pinfunction "1_1") (pintype "passive"))
      (node (ref "TP33") (pin "1") (pinfunction "G9_1") (pintype "passive"))
      (node (ref "U2") (pin "3") (pinfunction "0V_3") (pintype "power_in"))
      (node (ref "U5") (pin "5") (pinfunction "GND_5") (pintype "power_in"))
      (node (ref "U6") (pin "15") (pinfunction "GND2_15") (pintype "power_in"))
      (node (ref "U6") (pin "9") (pinfunction "GND2_9") (pintype "power_in"))
      (node (ref "ZD2") (pin "1") (pinfunction "A_1") (pintype "passive"))
      (node (ref "ZD3") (pin "1") (pinfunction "A_1") (pintype "passive"))
    )
    (net (code "24") (name "GND_III") (class "Default")
      (node (ref "C1") (pin "2") (pinfunction "-_2") (pintype "passive"))
      (node (ref "C10") (pin "1") (pinfunction "1_1") (pintype "passive"))
      (node (ref "C11") (pin "2") (pinfunction "-_2") (pintype "passive"))
      (node (ref "C12") (pin "2") (pinfunction "2_2") (pintype "passive"))
      (node (ref "C13") (pin "2") (pinfunction "2_2") (pintype "passive"))
      (node (ref "C16") (pin "2") (pinfunction "2_2") (pintype "passive"))
      (node (ref "C17") (pin "1") (pinfunction "1_1") (pintype "passive"))
      (node (ref "C19") (pin "2") (pinfunction "2_2") (pintype "passive"))
      (node (ref "C2") (pin "2") (pinfunction "2_2") (pintype "passive"))
      (node (ref "C20") (pin "1") (pinfunction "1_1") (pintype "passive"))
      (node (ref "C21") (pin "2") (pinfunction "-_2") (pintype "passive"))
      (node (ref "C22") (pin "1") (pinfunction "1_1") (pintype "passive"))
      (node (ref "C24") (pin "2") (pinfunction "-_2") (pintype "passive"))
      (node (ref "C25") (pin "2") (pinfunction "2_2") (pintype "passive"))
      (node (ref "C26") (pin "2") (pinfunction "-_2") (pintype "passive"))
      (node (ref "C27") (pin "2") (pinfunction "-_2") (pintype "passive"))
      (node (ref "C28") (pin "2") (pinfunction "-_2") (pintype "passive"))
      (node (ref "C29") (pin "1") (pinfunction "1_1") (pintype "passive"))
      (node (ref "C3") (pin "2") (pinfunction "2_2") (pintype "passive"))
      (node (ref "C30") (pin "2") (pinfunction "-_2") (pintype "passive"))
      (node (ref "C31") (pin "2") (pinfunction "2_2") (pintype "passive"))
      (node (ref "C32") (pin "1") (pinfunction "1_1") (pintype "passive"))
      (node (ref "C33") (pin "2") (pinfunction "-_2") (pintype "passive"))
      (node (ref "C34") (pin "1") (pinfunction "1_1") (pintype "passive"))
      (node (ref "C35") (pin "1") (pinfunction "1_1") (pintype "passive"))
      (node (ref "C36") (pin "1") (pinfunction "1_1") (pintype "passive"))
      (node (ref "C37") (pin "1") (pinfunction "1_1") (pintype "passive"))
      (node (ref "C38") (pin "1") (pinfunction "1_1") (pintype "passive"))
      (node (ref "C41") (pin "1") (pinfunction "1_1") (pintype "passive"))
      (node (ref "C42") (pin "1") (pinfunction "1_1") (pintype "passive"))
      (node (ref "C43") (pin "1") (pinfunction "1_1") (pintype "passive"))
      (node (ref "C45") (pin "1") (pinfunction "1_1") (pintype "passive"))
      (node (ref "C48") (pin "1") (pinfunction "1_1") (pintype "passive"))
      (node (ref "C49") (pin "1") (pinfunction "1_1") (pintype "passive"))
      (node (ref "C50") (pin "1") (pinfunction "1_1") (pintype "passive"))
      (node (ref "C51") (pin "1") (pinfunction "1_1") (pintype "passive"))
      (node (ref "C52") (pin "1") (pinfunction "1_1") (pintype "passive"))
      (node (ref "C54") (pin "2") (pinfunction "-_2") (pintype "passive"))
      (node (ref "C55") (pin "1") (pinfunction "1_1") (pintype "passive"))
      (node (ref "C6") (pin "2") (pinfunction "2_2") (pintype "passive"))
      (node (ref "C7") (pin "1") (pinfunction "1_1") (pintype "passive"))
      (node (ref "C9") (pin "2") (pinfunction "2_2") (pintype "passive"))
      (node (ref "D2") (pin "2") (pinfunction "K_2") (pintype "passive"))
      (node (ref "D3") (pin "2") (pinfunction "K_2") (pintype "passive"))
      (node (ref "D4") (pin "2") (pinfunction "K_2") (pintype "passive"))
      (node (ref "DA2") (pin "3") (pinfunction "EMITTER_3") (pintype "passive"))
      (node (ref "DA4") (pin "3") (pinfunction "EMITTER_3") (pintype "passive"))
      (node (ref "DD1") (pin "12") (pinfunction "GND_12") (pintype "passive"))
      (node (ref "DD4") (pin "12") (pinfunction "GND_12") (pintype "passive"))
      (node (ref "J1") (pin "6") (pinfunction "6_6") (pintype "passive"))
      (node (ref "P2") (pin "15") (pinfunction "15_15") (pintype "passive"))
      (node (ref "R1") (pin "1") (pinfunction "1_1") (pintype "passive"))
      (node (ref "R12") (pin "2") (pinfunction "2_2") (pintype "passive"))
      (node (ref "R16") (pin "2") (pinfunction "2_2") (pintype "passive"))
      (node (ref "R18") (pin "1") (pinfunction "1_1") (pintype "passive"))
      (node (ref "R2") (pin "1") (pinfunction "1_1") (pintype "passive"))
      (node (ref "R22") (pin "1") (pinfunction "1_1") (pintype "passive"))
      (node (ref "R23") (pin "1") (pinfunction "1_1") (pintype "passive"))
      (node (ref "R24") (pin "1") (pinfunction "1_1") (pintype "passive"))
      (node (ref "R28") (pin "2") (pinfunction "2_2") (pintype "passive"))
      (node (ref "R3") (pin "1") (pinfunction "1_1") (pintype "passive"))
      (node (ref "R30") (pin "1") (pinfunction "1_1") (pintype "passive"))
      (node (ref "R33") (pin "2") (pinfunction "2_2") (pintype "passive"))
      (node (ref "R37") (pin "2") (pinfunction "2_2") (pintype "passive"))
      (node (ref "R39") (pin "1") (pinfunction "1_1") (pintype "passive"))
      (node (ref "R55") (pin "1") (pinfunction "1_1") (pintype "passive"))
      (node (ref "R57") (pin "1") (pinfunction "1_1") (pintype "passive"))
      (node (ref "R61") (pin "2") (pinfunction "2_2") (pintype "passive"))
      (node (ref "R67") (pin "2") (pinfunction "2_2") (pintype "passive"))
      (node (ref "R68") (pin "1") (pinfunction "1_1") (pintype "passive"))
      (node (ref "R7") (pin "2") (pinfunction "2_2") (pintype "passive"))
      (node (ref "R76") (pin "2") (pinfunction "2_2") (pintype "passive"))
      (node (ref "R81") (pin "1") (pinfunction "1_1") (pintype "passive"))
      (node (ref "R82") (pin "1") (pinfunction "1_1") (pintype "passive"))
      (node (ref "R83") (pin "1") (pinfunction "1_1") (pintype "passive"))
      (node (ref "R9") (pin "1") (pinfunction "1_1") (pintype "passive"))
      (node (ref "TP3") (pin "1") (pinfunction "G9_1") (pintype "passive"))
      (node (ref "U1") (pin "3") (pinfunction "SD_3") (pintype "input"))
      (node (ref "U1") (pin "4") (pinfunction "GND_4") (pintype "power_in"))
      (node (ref "U10") (pin "2") (pinfunction "VSS_2") (pintype "power_in"))
      (node (ref "U2") (pin "1") (pinfunction "GND_1") (pintype "power_in"))
      (node (ref "U3") (pin "4") (pinfunction "GND_4") (pintype "power_in"))
      (node (ref "U4") (pin "1") (pinfunction "Ground_1") (pintype "power_in"))
      (node (ref "U6") (pin "2") (pinfunction "GND1_2") (pintype "power_in"))
      (node (ref "U6") (pin "8") (pinfunction "GND1_8") (pintype "power_in"))
      (node (ref "U7") (pin "5") (pinfunction "VSS/VSSA_5") (pintype "power_in"))
      (node (ref "U8") (pin "1") (pinfunction "Ground_1") (pintype "power_in"))
      (node (ref "U9") (pin "2") (pinfunction "VSS_2") (pintype "power_in"))
      (node (ref "VD11") (pin "1") (pinfunction "C_1") (pintype "passive"))
      (node (ref "VD12") (pin "2") (pinfunction "A_2") (pintype "passive"))
      (node (ref "VD13") (pin "2") (pinfunction "A_2") (pintype "passive"))
      (node (ref "VD5") (pin "1") (pinfunction "C_1") (pintype "passive"))
      (node (ref "VD6") (pin "2") (pinfunction "A_2") (pintype "passive"))
      (node (ref "VT1") (pin "3") (pinfunction "E_3") (pintype "passive"))
      (node (ref "VT2") (pin "3") (pinfunction "E_3") (pintype "passive"))
    )
    (net (code "25") (name "Net-(C26-+)") (class "Default")
      (node (ref "C26") (pin "1") (pinfunction "+_1") (pintype "passive"))
      (node (ref "JE1") (pin "1") (pinfunction "1_1") (pintype "passive"))
      (node (ref "L4") (pin "1") (pinfunction "1_1") (pintype "passive"))
      (node (ref "U1") (pin "8") (pinfunction "IN_8") (pintype "power_in"))
    )
    (net (code "26") (name "Net-(C27-+)") (class "Default")
      (node (ref "C27") (pin "1") (pinfunction "+_1") (pintype "passive"))
      (node (ref "C29") (pin "2") (pinfunction "2_2") (pintype "passive"))
      (node (ref "L4") (pin "2") (pinfunction "2_2") (pintype "passive"))
      (node (ref "TP25") (pin "1") (pinfunction "G9_1") (pintype "passive"))
      (node (ref "U4") (pin "3") (pinfunction "VIN_3") (pintype "power_in"))
    )
    (net (code "27") (name "Net-(C28-+)") (class "Default")
      (node (ref "C28") (pin "1") (pinfunction "+_1") (pintype "passive"))
      (node (ref "JE1") (pin "2") (pinfunction "2_2") (pintype "passive"))
      (node (ref "L3") (pin "2") (pinfunction "2_2") (pintype "passive"))
      (node (ref "R52") (pin "1") (pinfunction "1_1") (pintype "passive"))
    )
    (net (code "28") (name "Net-(C41-Pad2)") (class "Default")
      (node (ref "C41") (pin "2") (pinfunction "2_2") (pintype "passive"))
      (node (ref "R62") (pin "1") (pinfunction "1_1") (pintype "passive"))
      (node (ref "R63") (pin "2") (pinfunction "2_2") (pintype "passive"))
    )
    (net (code "29") (name "Net-(C48-Pad2)") (class "Default")
      (node (ref "C48") (pin "2") (pinfunction "2_2") (pintype "passive"))
      (node (ref "R72") (pin "1") (pinfunction "1_1") (pintype "passive"))
      (node (ref "R73") (pin "2") (pinfunction "2_2") (pintype "passive"))
    )
    (net (code "30") (name "Net-(D2-A)") (class "Default")
      (node (ref "D2") (pin "1") (pinfunction "A_1") (pintype "passive"))
      (node (ref "R54") (pin "1") (pinfunction "1_1") (pintype "passive"))
    )
    (net (code "31") (name "Net-(D3-A)") (class "Default")
      (node (ref "D3") (pin "1") (pinfunction "A_1") (pintype "passive"))
      (node (ref "R59") (pin "2") (pinfunction "2_2") (pintype "passive"))
    )
    (net (code "32") (name "Net-(D4-A)") (class "Default")
      (node (ref "D4") (pin "1") (pinfunction "A_1") (pintype "passive"))
      (node (ref "R65") (pin "2") (pinfunction "2_2") (pintype "passive"))
    )
    (net (code "33") (name "Net-(DA1-CATHODE)") (class "Default")
      (node (ref "DA1") (pin "2") (pinfunction "CATHODE_2") (pintype "passive"))
      (node (ref "R1") (pin "2") (pinfunction "2_2") (pintype "passive"))
    )
    (net (code "34") (name "Net-(DA1-COLLECTOR)") (class "Default")
      (node (ref "C2") (pin "1") (pinfunction "1_1") (pintype "passive"))
      (node (ref "C6") (pin "1") (pinfunction "1_1") (pintype "passive"))
      (node (ref "DA1") (pin "4") (pinfunction "COLLECTOR_4") (pintype "passive"))
      (node (ref "DD1") (pin "1") (pinfunction "INV_IN_1") (pintype "passive"))
      (node (ref "R2") (pin "2") (pinfunction "2_2") (pintype "passive"))
      (node (ref "R20") (pin "2") (pinfunction "2_2") (pintype "passive"))
      (node (ref "TP1") (pin "1") (pinfunction "G9_1") (pintype "passive"))
    )
    (net (code "35") (name "Net-(DA1-EMITTER)") (class "Default")
      (node (ref "DA1") (pin "3") (pinfunction "EMITTER_3") (pintype "passive"))
      (node (ref "R3") (pin "2") (pinfunction "2_2") (pintype "passive"))
    )
    (net (code "36") (name "Net-(DA2-ANODE)") (class "Default")
      (node (ref "DA2") (pin "1") (pinfunction "ANODE_1") (pintype "passive"))
      (node (ref "R4") (pin "1") (pinfunction "1_1") (pintype "passive"))
    )
    (net (code "37") (name "Net-(DA2-CATHODE)") (class "Default")
      (node (ref "DA2") (pin "2") (pinfunction "CATHODE_2") (pintype "passive"))
      (node (ref "TP2") (pin "1") (pinfunction "G9_1") (pintype "passive"))
      (node (ref "VT1") (pin "2") (pinfunction "C_2") (pintype "passive"))
    )
    (net (code "38") (name "Net-(DA3-CATHODE)") (class "Default")
      (node (ref "DA3") (pin "2") (pinfunction "CATHODE_2") (pintype "passive"))
      (node (ref "R22") (pin "2") (pinfunction "2_2") (pintype "passive"))
    )
    (net (code "39") (name "Net-(DA3-COLLECTOR)") (class "Default")
      (node (ref "C12") (pin "1") (pinfunction "1_1") (pintype "passive"))
      (node (ref "C16") (pin "1") (pinfunction "1_1") (pintype "passive"))
      (node (ref "DA3") (pin "4") (pinfunction "COLLECTOR_4") (pintype "passive"))
      (node (ref "DD4") (pin "1") (pinfunction "INV_IN_1") (pintype "passive"))
      (node (ref "R23") (pin "2") (pinfunction "2_2") (pintype "passive"))
      (node (ref "R41") (pin "2") (pinfunction "2_2") (pintype "passive"))
      (node (ref "TP12") (pin "1") (pinfunction "G9_1") (pintype "passive"))
    )
    (net (code "40") (name "Net-(DA3-EMITTER)") (class "Default")
      (node (ref "DA3") (pin "3") (pinfunction "EMITTER_3") (pintype "passive"))
      (node (ref "R24") (pin "2") (pinfunction "2_2") (pintype "passive"))
    )
    (net (code "41") (name "Net-(DA4-ANODE)") (class "Default")
      (node (ref "DA4") (pin "1") (pinfunction "ANODE_1") (pintype "passive"))
      (node (ref "R25") (pin "1") (pinfunction "1_1") (pintype "passive"))
    )
    (net (code "42") (name "Net-(DA4-CATHODE)") (class "Default")
      (node (ref "DA4") (pin "2") (pinfunction "CATHODE_2") (pintype "passive"))
      (node (ref "TP13") (pin "1") (pinfunction "G9_1") (pintype "passive"))
      (node (ref "VT2") (pin "2") (pinfunction "C_2") (pintype "passive"))
    )
    (net (code "43") (name "Net-(DD1-COMPENSATION)") (class "Default")
      (node (ref "DD1") (pin "9") (pinfunction "COMPENSATION_9") (pintype "passive"))
      (node (ref "R20") (pin "1") (pinfunction "1_1") (pintype "passive"))
    )
    (net (code "44") (name "Net-(DD1-CT)") (class "Default")
      (node (ref "DD1") (pin "5") (pinfunction "CT_5") (pintype "passive"))
      (node (ref "R14") (pin "1") (pinfunction "1_1") (pintype "passive"))
    )
    (net (code "45") (name "Net-(DD1-DISCHARGE)") (class "Default")
      (node (ref "DD1") (pin "7") (pinfunction "DISCHARGE_7") (pintype "passive"))
      (node (ref "R17") (pin "1") (pinfunction "1_1") (pintype "passive"))
    )
    (net (code "46") (name "Net-(DD1-NON_INV_IN)") (class "Default")
      (node (ref "DD1") (pin "2") (pinfunction "NON_INV_IN_2") (pintype "passive"))
      (node (ref "R7") (pin "1") (pinfunction "1_1") (pintype "passive"))
      (node (ref "R8") (pin "2") (pinfunction "2_2") (pintype "passive"))
      (node (ref "TP8") (pin "1") (pinfunction "G9_1") (pintype "passive"))
    )
    (net (code "47") (name "Net-(DD1-RT)") (class "Default")
      (node (ref "DD1") (pin "6") (pinfunction "RT_6") (pintype "passive"))
      (node (ref "R16") (pin "1") (pinfunction "1_1") (pintype "passive"))
    )
    (net (code "48") (name "Net-(DD1-SHUT_DOWN)") (class "Default")
      (node (ref "C10") (pin "2") (pinfunction "2_2") (pintype "passive"))
      (node (ref "DD1") (pin "10") (pinfunction "SHUT_DOWN_10") (pintype "passive"))
      (node (ref "R15") (pin "1") (pinfunction "1_1") (pintype "passive"))
      (node (ref "R18") (pin "2") (pinfunction "2_2") (pintype "passive"))
    )
    (net (code "49") (name "Net-(DD1-SOFT_START)") (class "Default")
      (node (ref "C9") (pin "1") (pinfunction "1_1") (pintype "passive"))
      (node (ref "DD1") (pin "8") (pinfunction "SOFT_START_8") (pintype "passive"))
    )
    (net (code "50") (name "Net-(DD1-SYNC)") (class "Default")
      (node (ref "DD1") (pin "3") (pinfunction "SYNC_3") (pintype "passive"))
      (node (ref "R12") (pin "1") (pinfunction "1_1") (pintype "passive"))
    )
    (net (code "51") (name "Net-(DD1-V_REF)") (class "Default")
      (node (ref "C3") (pin "1") (pinfunction "1_1") (pintype "passive"))
      (node (ref "DD1") (pin "16") (pinfunction "V_REF_16") (pintype "passive"))
      (node (ref "R2") (pin "3") (pinfunction "3_3") (pintype "passive"))
      (node (ref "R8") (pin "1") (pinfunction "1_1") (pintype "passive"))
    )
    (net (code "52") (name "Net-(DD2-VIN-)") (class "Default")
      (node (ref "DD2") (pin "4") (pinfunction "VIN-_4") (pintype "passive"))
      (node (ref "R11") (pin "2") (pinfunction "2_2") (pintype "passive"))
      (node (ref "R13") (pin "1") (pinfunction "1_1") (pintype "passive"))
    )
    (net (code "53") (name "Net-(DD2-VOUT)") (class "Default")
      (node (ref "DD2") (pin "1") (pinfunction "VOUT_1") (pintype "passive"))
      (node (ref "R11") (pin "1") (pinfunction "1_1") (pintype "passive"))
      (node (ref "R6") (pin "1") (pinfunction "1_1") (pintype "passive"))
    )
    (net (code "54") (name "Net-(DD2-VSS)") (class "Default")
      (node (ref "C4") (pin "1") (pinfunction "1_1") (pintype "passive"))
      (node (ref "C5") (pin "1") (pinfunction "1_1") (pintype "passive"))
      (node (ref "C8") (pin "2") (pinfunction "2_2") (pintype "passive"))
      (node (ref "DD2") (pin "2") (pinfunction "VSS_2") (pintype "passive"))
      (node (ref "DD3") (pin "2") (pinfunction "VSS_2") (pintype "passive"))
      (node (ref "R13") (pin "2") (pinfunction "2_2") (pintype "passive"))
      (node (ref "R21") (pin "2") (pinfunction "2_2") (pintype "passive"))
      (node (ref "VD3") (pin "2") (pinfunction "A_2") (pintype "passive"))
      (node (ref "VD4") (pin "1") (pinfunction "C_1") (pintype "passive"))
    )
    (net (code "55") (name "Net-(DD3-VIN+)") (class "Default")
      (node (ref "C8") (pin "1") (pinfunction "1_1") (pintype "passive"))
      (node (ref "DD3") (pin "3") (pinfunction "VIN+_3") (pintype "passive"))
      (node (ref "R10") (pin "2") (pinfunction "2_2") (pintype "passive"))
      (node (ref "TP9") (pin "1") (pinfunction "G9_1") (pintype "passive"))
      (node (ref "VD1") (pin "2") (pinfunction "A_2") (pintype "passive"))
      (node (ref "VD2") (pin "2") (pinfunction "A_2") (pintype "passive"))
    )
    (net (code "56") (name "Net-(DD3-VIN-)") (class "Default")
      (node (ref "DD3") (pin "4") (pinfunction "VIN-_4") (pintype "passive"))
      (node (ref "R19") (pin "2") (pinfunction "2_2") (pintype "passive"))
      (node (ref "R21") (pin "1") (pinfunction "1_1") (pintype "passive"))
    )
    (net (code "57") (name "Net-(DD3-VOUT)") (class "Default")
      (node (ref "DD3") (pin "1") (pinfunction "VOUT_1") (pintype "passive"))
      (node (ref "R14") (pin "2") (pinfunction "2_2") (pintype "passive"))
      (node (ref "R19") (pin "1") (pinfunction "1_1") (pintype "passive"))
      (node (ref "TP6") (pin "1") (pinfunction "G9_1") (pintype "passive"))
    )
    (net (code "58") (name "Net-(DD4-COMPENSATION)") (class "Default")
      (node (ref "DD4") (pin "9") (pinfunction "COMPENSATION_9") (pintype "passive"))
      (node (ref "R41") (pin "1") (pinfunction "1_1") (pintype "passive"))
    )
    (net (code "59") (name "Net-(DD4-CT)") (class "Default")
      (node (ref "DD4") (pin "5") (pinfunction "CT_5") (pintype "passive"))
      (node (ref "R35") (pin "1") (pinfunction "1_1") (pintype "passive"))
    )
    (net (code "60") (name "Net-(DD4-DISCHARGE)") (class "Default")
      (node (ref "DD4") (pin "7") (pinfunction "DISCHARGE_7") (pintype "passive"))
      (node (ref "R38") (pin "1") (pinfunction "1_1") (pintype "passive"))
    )
    (net (code "61") (name "Net-(DD4-NON_INV_IN)") (class "Default")
      (node (ref "DD4") (pin "2") (pinfunction "NON_INV_IN_2") (pintype "passive"))
      (node (ref "R28") (pin "1") (pinfunction "1_1") (pintype "passive"))
      (node (ref "R29") (pin "2") (pinfunction "2_2") (pintype "passive"))
      (node (ref "TP19") (pin "1") (pinfunction "G9_1") (pintype "passive"))
    )
    (net (code "62") (name "Net-(DD4-RT)") (class "Default")
      (node (ref "DD4") (pin "6") (pinfunction "RT_6") (pintype "passive"))
      (node (ref "R37") (pin "1") (pinfunction "1_1") (pintype "passive"))
    )
    (net (code "63") (name "Net-(DD4-SHUT_DOWN)") (class "Default")
      (node (ref "C20") (pin "2") (pinfunction "2_2") (pintype "passive"))
      (node (ref "DD4") (pin "10") (pinfunction "SHUT_DOWN_10") (pintype "passive"))
      (node (ref "R36") (pin "1") (pinfunction "1_1") (pintype "passive"))
      (node (ref "R39") (pin "2") (pinfunction "2_2") (pintype "passive"))
    )
    (net (code "64") (name "Net-(DD4-SOFT_START)") (class "Default")
      (node (ref "C19") (pin "1") (pinfunction "1_1") (pintype "passive"))
      (node (ref "DD4") (pin "8") (pinfunction "SOFT_START_8") (pintype "passive"))
    )
    (net (code "65") (name "Net-(DD4-SYNC)") (class "Default")
      (node (ref "DD4") (pin "3") (pinfunction "SYNC_3") (pintype "passive"))
      (node (ref "R33") (pin "1") (pinfunction "1_1") (pintype "passive"))
    )
    (net (code "66") (name "Net-(DD4-V_REF)") (class "Default")
      (node (ref "C13") (pin "1") (pinfunction "1_1") (pintype "passive"))
      (node (ref "DD4") (pin "16") (pinfunction "V_REF_16") (pintype "passive"))
      (node (ref "R23") (pin "3") (pinfunction "3_3") (pintype "passive"))
      (node (ref "R29") (pin "1") (pinfunction "1_1") (pintype "passive"))
    )
    (net (code "67") (name "Net-(DD5-VIN-)") (class "Default")
      (node (ref "DD5") (pin "4") (pinfunction "VIN-_4") (pintype "passive"))
      (node (ref "R32") (pin "2") (pinfunction "2_2") (pintype "passive"))
      (node (ref "R34") (pin "1") (pinfunction "1_1") (pintype "passive"))
    )
    (net (code "68") (name "Net-(DD5-VOUT)") (class "Default")
      (node (ref "DD5") (pin "1") (pinfunction "VOUT_1") (pintype "passive"))
      (node (ref "R27") (pin "1") (pinfunction "1_1") (pintype "passive"))
      (node (ref "R32") (pin "1") (pinfunction "1_1") (pintype "passive"))
    )
    (net (code "69") (name "Net-(DD5-VSS)") (class "Default")
      (node (ref "C14") (pin "1") (pinfunction "1_1") (pintype "passive"))
      (node (ref "C15") (pin "1") (pinfunction "1_1") (pintype "passive"))
      (node (ref "C18") (pin "2") (pinfunction "2_2") (pintype "passive"))
      (node (ref "DD5") (pin "2") (pinfunction "VSS_2") (pintype "passive"))
      (node (ref "DD6") (pin "2") (pinfunction "VSS_2") (pintype "passive"))
      (node (ref "R34") (pin "2") (pinfunction "2_2") (pintype "passive"))
      (node (ref "R42") (pin "2") (pinfunction "2_2") (pintype "passive"))
      (node (ref "VD10") (pin "1") (pinfunction "C_1") (pintype "passive"))
      (node (ref "VD9") (pin "2") (pinfunction "A_2") (pintype "passive"))
    )
    (net (code "70") (name "Net-(DD6-VIN+)") (class "Default")
      (node (ref "C18") (pin "1") (pinfunction "1_1") (pintype "passive"))
      (node (ref "DD6") (pin "3") (pinfunction "VIN+_3") (pintype "passive"))
      (node (ref "R31") (pin "2") (pinfunction "2_2") (pintype "passive"))
      (node (ref "TP20") (pin "1") (pinfunction "G9_1") (pintype "passive"))
      (node (ref "VD7") (pin "2") (pinfunction "A_2") (pintype "passive"))
      (node (ref "VD8") (pin "2") (pinfunction "A_2") (pintype "passive"))
    )
    (net (code "71") (name "Net-(DD6-VIN-)") (class "Default")
      (node (ref "DD6") (pin "4") (pinfunction "VIN-_4") (pintype "passive"))
      (node (ref "R40") (pin "2") (pinfunction "2_2") (pintype "passive"))
      (node (ref "R42") (pin "1") (pinfunction "1_1") (pintype "passive"))
    )
    (net (code "72") (name "Net-(DD6-VOUT)") (class "Default")
      (node (ref "DD6") (pin "1") (pinfunction "VOUT_1") (pintype "passive"))
      (node (ref "R35") (pin "2") (pinfunction "2_2") (pintype "passive"))
      (node (ref "R40") (pin "1") (pinfunction "1_1") (pintype "passive"))
      (node (ref "TP17") (pin "1") (pinfunction "G9_1") (pintype "passive"))
    )
    (net (code "73") (name "Net-(L1-Pad1)") (class "Default")
      (node (ref "L1") (pin "1") (pinfunction "1_1") (pintype "passive"))
      (node (ref "R4") (pin "2") (pinfunction "2_2") (pintype "passive"))
    )
    (net (code "74") (name "Net-(L2-Pad1)") (class "Default")
      (node (ref "L2") (pin "1") (pinfunction "1_1") (pintype "passive"))
      (node (ref "R25") (pin "2") (pinfunction "2_2") (pintype "passive"))
    )
    (net (code "75") (name "Net-(TP5-G9)") (class "Default")
      (node (ref "R10") (pin "1") (pinfunction "1_1") (pintype "passive"))
      (node (ref "R6") (pin "2") (pinfunction "2_2") (pintype "passive"))
      (node (ref "R6") (pin "3") (pinfunction "3_3") (pintype "passive"))
      (node (ref "TP5") (pin "1") (pinfunction "G9_1") (pintype "passive"))
      (node (ref "VD1") (pin "1") (pinfunction "C_1") (pintype "passive"))
    )
    (net (code "76") (name "Net-(TP11-G9)") (class "Default")
      (node (ref "R17") (pin "2") (pinfunction "2_2") (pintype "passive"))
      (node (ref "TP11") (pin "1") (pinfunction "G9_1") (pintype "passive"))
      (node (ref "VD2") (pin "1") (pinfunction "C_1") (pintype "passive"))
    )
    (net (code "77") (name "Net-(TP16-G9)") (class "Default")
      (node (ref "R27") (pin "2") (pinfunction "2_2") (pintype "passive"))
      (node (ref "R27") (pin "3") (pinfunction "3_3") (pintype "passive"))
      (node (ref "R31") (pin "1") (pinfunction "1_1") (pintype "passive"))
      (node (ref "TP16") (pin "1") (pinfunction "G9_1") (pintype "passive"))
      (node (ref "VD7") (pin "1") (pinfunction "C_1") (pintype "passive"))
    )
    (net (code "78") (name "Net-(TP22-G9)") (class "Default")
      (node (ref "R38") (pin "2") (pinfunction "2_2") (pintype "passive"))
      (node (ref "TP22") (pin "1") (pinfunction "G9_1") (pintype "passive"))
      (node (ref "VD8") (pin "1") (pinfunction "C_1") (pintype "passive"))
    )
    (net (code "79") (name "Net-(TP24-G9)") (class "Default")
      (node (ref "L3") (pin "1") (pinfunction "1_1") (pintype "passive"))
      (node (ref "TP24") (pin "1") (pinfunction "G9_1") (pintype "passive"))
      (node (ref "U3") (pin "2") (pinfunction "SWE_2") (pintype "open_emitter"))
      (node (ref "VD13") (pin "1") (pinfunction "C_1") (pintype "passive"))
    )
    (net (code "80") (name "Net-(TP26-G9)") (class "Default")
      (node (ref "R46") (pin "1") (pinfunction "1_1") (pintype "passive"))
      (node (ref "R50") (pin "1") (pinfunction "1_1") (pintype "passive"))
      (node (ref "TP26") (pin "1") (pinfunction "G9_1") (pintype "passive"))
      (node (ref "U5") (pin "4") (pinfunction "DI_4") (pintype "input"))
    )
    (net (code "81") (name "Net-(TP30-G9)") (class "Default")
      (node (ref "R53") (pin "2") (pinfunction "2_2") (pintype "passive"))
      (node (ref "TP30") (pin "1") (pinfunction "G9_1") (pintype "passive"))
      (node (ref "U5") (pin "2") (pinfunction "~{RE}_2") (pintype "input"))
      (node (ref "U5") (pin "3") (pinfunction "DE_3") (pintype "input"))
      (node (ref "U6") (pin "12") (pinfunction "VOC_12") (pintype "tri_state"))
    )
    (net (code "82") (name "Net-(TP32-G9)") (class "Default")
      (node (ref "R47") (pin "1") (pinfunction "1_1") (pintype "passive"))
      (node (ref "R51") (pin "1") (pinfunction "1_1") (pintype "passive"))
      (node (ref "TP32") (pin "1") (pinfunction "G9_1") (pintype "passive"))
      (node (ref "U5") (pin "1") (pinfunction "RO_1") (pintype "output"))
    )
    (net (code "83") (name "Net-(TP37-G9)") (class "Default")
      (node (ref "C39") (pin "2") (pinfunction "2_2") (pintype "passive"))
      (node (ref "C43") (pin "2") (pinfunction "2_2") (pintype "passive"))
      (node (ref "R60") (pin "2") (pinfunction "2_2") (pintype "passive"))
      (node (ref "R68") (pin "2") (pinfunction "2_2") (pintype "passive"))
      (node (ref "TP37") (pin "1") (pinfunction "G9_1") (pintype "passive"))
      (node (ref "U9") (pin "3") (pinfunction "VIN+_3") (pintype "input"))
    )
    (net (code "84") (name "Net-(TP38-G9)") (class "Default")
      (node (ref "C42") (pin "2") (pinfunction "2_2") (pintype "passive"))
      (node (ref "R63") (pin "1") (pinfunction "1_1") (pintype "passive"))
      (node (ref "R64") (pin "2") (pinfunction "2_2") (pintype "passive"))
      (node (ref "R67") (pin "1") (pinfunction "1_1") (pintype "passive"))
      (node (ref "TP38") (pin "1") (pinfunction "G9_1") (pintype "passive"))
    )
    (net (code "85") (name "Net-(TP39-G9)") (class "Default")
      (node (ref "C44") (pin "2") (pinfunction "2_2") (pintype "passive"))
      (node (ref "R62") (pin "2") (pinfunction "2_2") (pintype "passive"))
      (node (ref "R69") (pin "2") (pinfunction "2_2") (pintype "passive"))
      (node (ref "TP39") (pin "1") (pinfunction "G9_1") (pintype "passive"))
      (node (ref "U9") (pin "1") (pinfunction "VOUT_1") (pintype "output"))
    )
    (net (code "86") (name "Net-(TP42-G9)") (class "Default")
      (node (ref "C39") (pin "1") (pinfunction "1_1") (pintype "passive"))
      (node (ref "C44") (pin "1") (pinfunction "1_1") (pintype "passive"))
      (node (ref "R66") (pin "2") (pinfunction "2_2") (pintype "passive"))
      (node (ref "R69") (pin "1") (pinfunction "1_1") (pintype "passive"))
      (node (ref "TP42") (pin "1") (pinfunction "G9_1") (pintype "passive"))
      (node (ref "U9") (pin "4") (pinfunction "VIN-_4") (pintype "input"))
    )
    (net (code "87") (name "Net-(TP45-G9)") (class "Default")
      (node (ref "C46") (pin "2") (pinfunction "2_2") (pintype "passive"))
      (node (ref "C51") (pin "2") (pinfunction "2_2") (pintype "passive"))
      (node (ref "R71") (pin "2") (pinfunction "2_2") (pintype "passive"))
      (node (ref "R81") (pin "2") (pinfunction "2_2") (pintype "passive"))
      (node (ref "TP45") (pin "1") (pinfunction "G9_1") (pintype "passive"))
      (node (ref "U10") (pin "3") (pinfunction "VIN+_3") (pintype "input"))
    )
    (net (code "88") (name "Net-(TP47-G9)") (class "Default")
      (node (ref "C49") (pin "2") (pinfunction "2_2") (pintype "passive"))
      (node (ref "R73") (pin "1") (pinfunction "1_1") (pintype "passive"))
      (node (ref "R74") (pin "2") (pinfunction "2_2") (pintype "passive"))
      (node (ref "R76") (pin "1") (pinfunction "1_1") (pintype "passive"))
      (node (ref "TP47") (pin "1") (pinfunction "G9_1") (pintype "passive"))
    )
    (net (code "89") (name "Net-(TP48-G9)") (class "Default")
      (node (ref "C53") (pin "2") (pinfunction "2_2") (pintype "passive"))
      (node (ref "R72") (pin "2") (pinfunction "2_2") (pintype "passive"))
      (node (ref "R84") (pin "2") (pinfunction "2_2") (pintype "passive"))
      (node (ref "TP48") (pin "1") (pinfunction "G9_1") (pintype "passive"))
      (node (ref "U10") (pin "1") (pinfunction "VOUT_1") (pintype "output"))
    )
    (net (code "90") (name "Net-(TP51-G9)") (class "Default")
      (node (ref "C46") (pin "1") (pinfunction "1_1") (pintype "passive"))
      (node (ref "C53") (pin "1") (pinfunction "1_1") (pintype "passive"))
      (node (ref "R75") (pin "2") (pinfunction "2_2") (pintype "passive"))
      (node (ref "R84") (pin "1") (pinfunction "1_1") (pintype "passive"))
      (node (ref "TP51") (pin "1") (pinfunction "G9_1") (pintype "passive"))
      (node (ref "U10") (pin "4") (pinfunction "VIN-_4") (pintype "input"))
    )
    (net (code "91") (name "Net-(U1-FB)") (class "Default")
      (node (ref "U1") (pin "6") (pinfunction "VTAP_6") (pintype "passive"))
      (node (ref "U1") (pin "7") (pinfunction "FB_7") (pintype "input"))
    )
    (net (code "92") (name "Net-(U1-~{ERR})") (class "Default")
      (node (ref "R43") (pin "2") (pinfunction "2_2") (pintype "passive"))
      (node (ref "U1") (pin "5") (pinfunction "~{ERR}_5") (pintype "open_collector"))
    )
    (net (code "93") (name "Net-(U3-CII)") (class "Default")
      (node (ref "R52") (pin "2") (pinfunction "2_2") (pintype "passive"))
      (node (ref "R57") (pin "2") (pinfunction "2_2") (pintype "passive"))
      (node (ref "U3") (pin "5") (pinfunction "CII_5") (pintype "input"))
    )
    (net (code "94") (name "Net-(U3-DRC)") (class "Default")
      (node (ref "R49") (pin "2") (pinfunction "2_2") (pintype "passive"))
      (node (ref "U3") (pin "1") (pinfunction "SWC_1") (pintype "open_collector"))
      (node (ref "U3") (pin "7") (pinfunction "IPK_7") (pintype "passive"))
      (node (ref "U3") (pin "8") (pinfunction "DRC_8") (pintype "open_collector"))
    )
    (net (code "95") (name "Net-(U3-TC)") (class "Default")
      (node (ref "C25") (pin "1") (pinfunction "1_1") (pintype "passive"))
      (node (ref "U3") (pin "3") (pinfunction "TC_3") (pintype "passive"))
    )
    (net (code "96") (name "Net-(U5-A)") (class "Default")
      (node (ref "P1") (pin "3") (pinfunction "3_3") (pintype "passive"))
      (node (ref "R44") (pin "1") (pinfunction "1_1") (pintype "passive"))
      (node (ref "U5") (pin "6") (pinfunction "A_6") (pintype "bidirectional"))
      (node (ref "ZD1") (pin "2") (pinfunction "A_2") (pintype "passive"))
      (node (ref "ZD2") (pin "2") (pinfunction "A_2") (pintype "passive"))
    )
    (net (code "97") (name "Net-(U5-B)") (class "Default")
      (node (ref "P1") (pin "1") (pinfunction "1_1") (pintype "passive"))
      (node (ref "R56") (pin "2") (pinfunction "2_2") (pintype "passive"))
      (node (ref "U5") (pin "7") (pinfunction "B_7") (pintype "bidirectional"))
      (node (ref "ZD1") (pin "1") (pinfunction "A_1") (pintype "passive"))
      (node (ref "ZD3") (pin "2") (pinfunction "A_2") (pintype "passive"))
    )
    (net (code "98") (name "Net-(U6-VID)") (class "Default")
      (node (ref "R51") (pin "2") (pinfunction "2_2") (pintype "passive"))
      (node (ref "U6") (pin "11") (pinfunction "VID_11") (pintype "input"))
    )
    (net (code "99") (name "Net-(U6-VOB)") (class "Default")
      (node (ref "R50") (pin "2") (pinfunction "2_2") (pintype "passive"))
      (node (ref "U6") (pin "13") (pinfunction "VOB_13") (pintype "tri_state"))
    )
    (net (code "100") (name "Net-(U7-PA12[PA10])") (class "Default")
      (node (ref "R59") (pin "1") (pinfunction "1_1") (pintype "passive"))
      (node (ref "U7") (pin "17") (pinfunction "PA12[PA10]_17") (pintype "bidirectional"))
    )
    (net (code "101") (name "Net-(U7-PC15-OSC32_OUT)") (class "Default")
      (node (ref "R65") (pin "1") (pinfunction "1_1") (pintype "passive"))
      (node (ref "U7") (pin "3") (pinfunction "PC15-OSC32_OUT_3") (pintype "bidirectional"))
    )
    (net (code "102") (name "Net-(U7-~{RST})") (class "Default")
      (node (ref "C34") (pin "2") (pinfunction "2_2") (pintype "passive"))
      (node (ref "R58") (pin "2") (pinfunction "2_2") (pintype "passive"))
      (node (ref "U7") (pin "6") (pinfunction "~{RST}_6") (pintype "input"))
    )
    (net (code "103") (name "Net-(VD3-C)") (class "Default")
      (node (ref "VD3") (pin "1") (pinfunction "C_1") (pintype "passive"))
      (node (ref "VD5") (pin "2") (pinfunction "A_2") (pintype "passive"))
    )
    (net (code "104") (name "Net-(VD4-A)") (class "Default")
      (node (ref "VD4") (pin "2") (pinfunction "A_2") (pintype "passive"))
      (node (ref "VD6") (pin "1") (pinfunction "C_1") (pintype "passive"))
    )
    (net (code "105") (name "Net-(VD10-A)") (class "Default")
      (node (ref "VD10") (pin "2") (pinfunction "A_2") (pintype "passive"))
      (node (ref "VD12") (pin "1") (pinfunction "C_1") (pintype "passive"))
    )
    (net (code "106") (name "Net-(VD11-A)") (class "Default")
      (node (ref "VD11") (pin "2") (pinfunction "A_2") (pintype "passive"))
      (node (ref "VD9") (pin "1") (pinfunction "C_1") (pintype "passive"))
    )
    (net (code "107") (name "Net-(VT1-B)") (class "Default")
      (node (ref "R5") (pin "2") (pinfunction "2_2") (pintype "passive"))
      (node (ref "VT1") (pin "1") (pinfunction "B_1") (pintype "passive"))
    )
    (net (code "108") (name "Net-(VT2-B)") (class "Default")
      (node (ref "R26") (pin "2") (pinfunction "2_2") (pintype "passive"))
      (node (ref "VT2") (pin "1") (pinfunction "B_1") (pintype "passive"))
    )
    (net (code "109") (name "OUT_A1") (class "Default")
      (node (ref "DD1") (pin "11") (pinfunction "OUT_A_11") (pintype "passive"))
      (node (ref "P2") (pin "1") (pinfunction "1_1") (pintype "passive"))
      (node (ref "TP10") (pin "1") (pinfunction "G9_1") (pintype "passive"))
    )
    (net (code "110") (name "OUT_A2") (class "Default")
      (node (ref "DD4") (pin "11") (pinfunction "OUT_A_11") (pintype "passive"))
      (node (ref "P2") (pin "3") (pinfunction "3_3") (pintype "passive"))
      (node (ref "TP21") (pin "1") (pinfunction "G9_1") (pintype "passive"))
    )
    (net (code "111") (name "OUT_B1") (class "Default")
      (node (ref "DD1") (pin "14") (pinfunction "OUT_B_14") (pintype "passive"))
      (node (ref "P2") (pin "2") (pinfunction "2_2") (pintype "passive"))
      (node (ref "TP7") (pin "1") (pinfunction "G9_1") (pintype "passive"))
    )
    (net (code "112") (name "OUT_B2") (class "Default")
      (node (ref "DD4") (pin "14") (pinfunction "OUT_B_14") (pintype "passive"))
      (node (ref "P2") (pin "4") (pinfunction "4_4") (pintype "passive"))
      (node (ref "TP18") (pin "1") (pinfunction "G9_1") (pintype "passive"))
    )
    (net (code "113") (name "PWM_1") (class "Default")
      (node (ref "DD2") (pin "3") (pinfunction "VIN+_3") (pintype "passive"))
      (node (ref "R9") (pin "2") (pinfunction "2_2") (pintype "passive"))
      (node (ref "TP4") (pin "1") (pinfunction "G9_1") (pintype "passive"))
      (node (ref "U7") (pin "15") (pinfunction "PB0/PB1/PB2/PA8_15") (pintype "bidirectional"))
    )
    (net (code "114") (name "PWM_2") (class "Default")
      (node (ref "DD5") (pin "3") (pinfunction "VIN+_3") (pintype "passive"))
      (node (ref "R30") (pin "2") (pinfunction "2_2") (pintype "passive"))
      (node (ref "TP15") (pin "1") (pinfunction "G9_1") (pintype "passive"))
      (node (ref "U7") (pin "13") (pinfunction "PA6_13") (pintype "bidirectional"))
    )
    (net (code "115") (name "PWM_SET_1") (class "Default")
      (node (ref "DA1") (pin "1") (pinfunction "ANODE_1") (pintype "passive"))
      (node (ref "U7") (pin "16") (pinfunction "PA11[PA9]_16") (pintype "bidirectional"))
    )
    (net (code "116") (name "PWM_SET_2") (class "Default")
      (node (ref "DA3") (pin "1") (pinfunction "ANODE_1") (pintype "passive"))
      (node (ref "U7") (pin "14") (pinfunction "PA7_14") (pintype "bidirectional"))
    )
    (net (code "117") (name "SD_1") (class "Default")
      (node (ref "R5") (pin "1") (pinfunction "1_1") (pintype "passive"))
      (node (ref "U7") (pin "11") (pinfunction "PA4_11") (pintype "bidirectional"))
    )
    (net (code "118") (name "SD_2") (class "Default")
      (node (ref "R26") (pin "1") (pinfunction "1_1") (pintype "passive"))
      (node (ref "U7") (pin "12") (pinfunction "PA5_12") (pintype "bidirectional"))
    )
    (net (code "119") (name "SD_G_1") (class "Default")
      (node (ref "DA2") (pin "4") (pinfunction "COLLECTOR_4") (pintype "passive"))
      (node (ref "P2") (pin "12") (pinfunction "12_12") (pintype "passive"))
      (node (ref "R15") (pin "2") (pinfunction "2_2") (pintype "passive"))
      (node (ref "TP52") (pin "1") (pinfunction "G9_1") (pintype "passive"))
    )
    (net (code "120") (name "SD_G_2") (class "Default")
      (node (ref "DA4") (pin "4") (pinfunction "COLLECTOR_4") (pintype "passive"))
      (node (ref "P2") (pin "13") (pinfunction "13_13") (pintype "passive"))
      (node (ref "R36") (pin "2") (pinfunction "2_2") (pintype "passive"))
      (node (ref "TP53") (pin "1") (pinfunction "G9_1") (pintype "passive"))
    )
    (net (code "121") (name "unconnected-(DD1-OSC_OUT-Pad4)") (class "Default")
      (node (ref "DD1") (pin "4") (pinfunction "OSC_OUT_4") (pintype "passive"))
    )
    (net (code "122") (name "unconnected-(DD4-OSC_OUT-Pad4)") (class "Default")
      (node (ref "DD4") (pin "4") (pinfunction "OSC_OUT_4") (pintype "passive"))
    )
    (net (code "123") (name "unconnected-(P2-Pad7)") (class "Default")
      (node (ref "P2") (pin "7") (pinfunction "7_7") (pintype "passive"))
    )
    (net (code "124") (name "unconnected-(U6-VIA-Pad3)") (class "Default")
      (node (ref "U6") (pin "3") (pinfunction "VIA_3") (pintype "input"))
    )
    (net (code "125") (name "unconnected-(U6-VOA-Pad14)") (class "Default")
      (node (ref "U6") (pin "14") (pinfunction "VOA_14") (pintype "tri_state"))
    )
  )
)
